# PCB.net
KiCad netlist of a schematic drawn in EAGLE
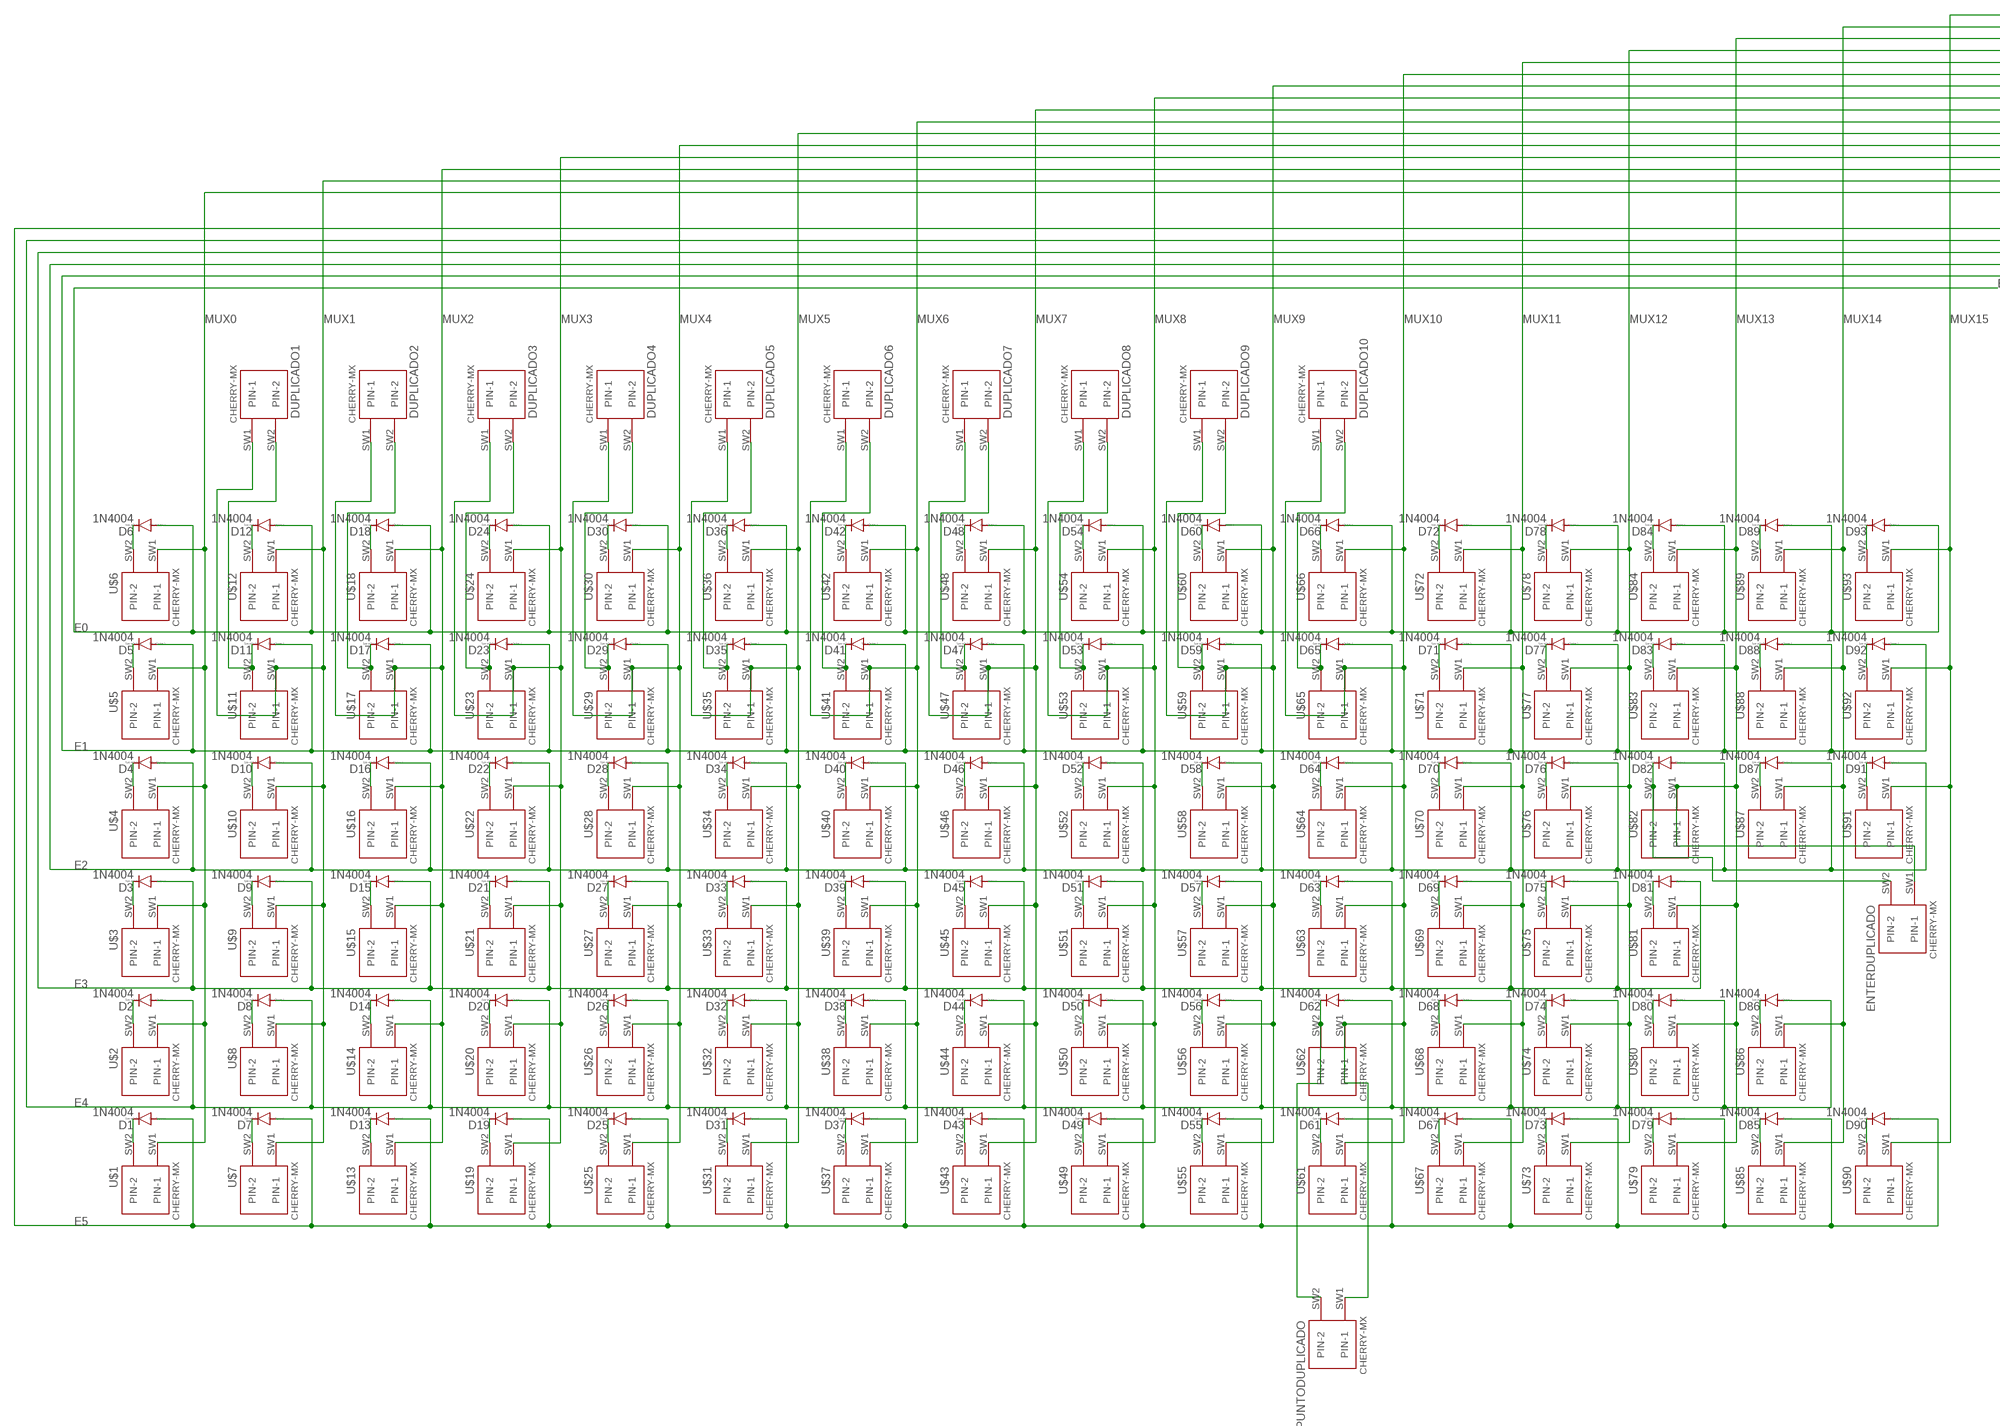
[diagram p0: schematic, sheet 1, part 1 of 2]
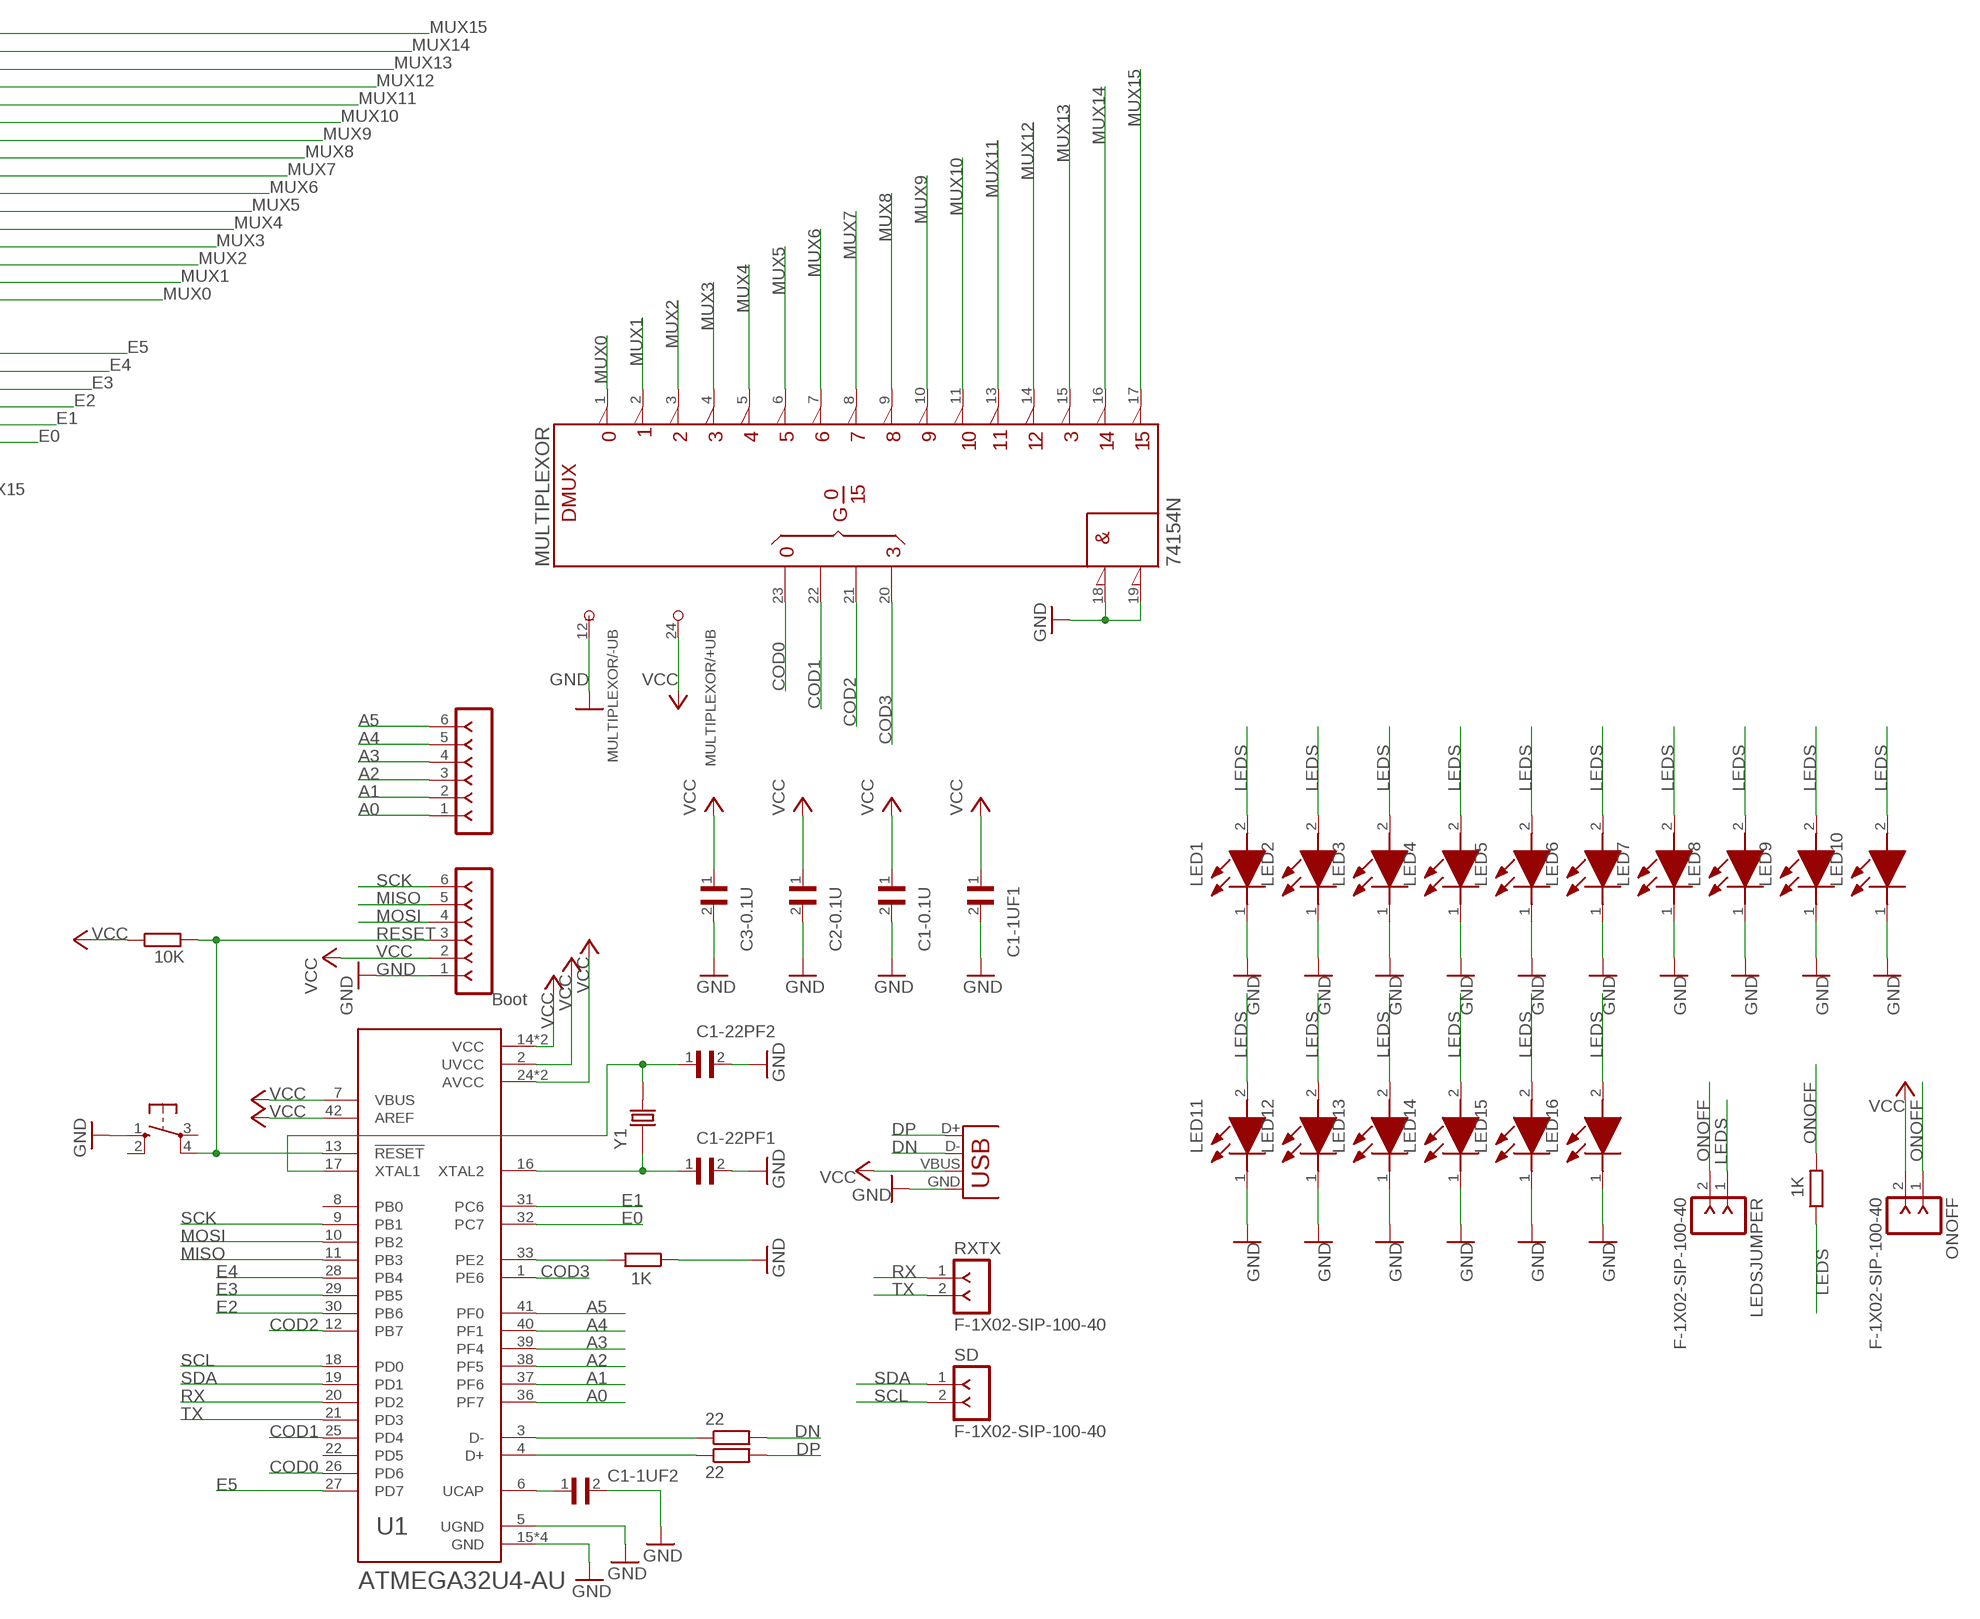
[diagram p1: schematic, sheet 1, part 2 of 2]

(export (version "E")
  (design (tool "Eeschema 10.0.6"))
  (components
    (comp (ref "ANALOG")
      (value "Boot")
      (footprint "eagle-import:SIP-100-06-32")
      (libsource (lib "eagle-import") (part "F-1X06-SIP-100-32"))
    )
    (comp (ref "BUTTON")
      (value "10-XX")
      (footprint "eagle-import:B3F-10XX")
      (fields (field (name "MPN") "B3F-1000"))
      (libsource (lib "eagle-import") (part "10-XX"))
    )
    (comp (ref "C1-0.1U")
      (value "RDE5C1H273J2M1H03A")
      (footprint "eagle-import:CAP_RDE5C1H273J2M1H03A")
      (fields (field (name "MF") "Murata Electronics"))
      (libsource (lib "eagle-import") (part "RDE5C1H273J2M1H03A"))
    )
    (comp (ref "C1-1UF1")
      (value "RDE5C1H273J2M1H03A")
      (footprint "eagle-import:CAP_RDE5C1H273J2M1H03A")
      (fields (field (name "MF") "Murata Electronics"))
      (libsource (lib "eagle-import") (part "RDE5C1H273J2M1H03A"))
    )
    (comp (ref "C1-1UF2")
      (value "RDE5C1H273J2M1H03A")
      (footprint "eagle-import:CAP_RDE5C1H273J2M1H03A")
      (fields (field (name "MF") "Murata Electronics"))
      (libsource (lib "eagle-import") (part "RDE5C1H273J2M1H03A"))
    )
    (comp (ref "C1-22PF1")
      (value "RDE5C1H273J2M1H03A")
      (footprint "eagle-import:CAP_RDE5C1H273J2M1H03A")
      (fields (field (name "MF") "Murata Electronics"))
      (libsource (lib "eagle-import") (part "RDE5C1H273J2M1H03A"))
    )
    (comp (ref "C1-22PF2")
      (value "RDE5C1H273J2M1H03A")
      (footprint "eagle-import:CAP_RDE5C1H273J2M1H03A")
      (fields (field (name "MF") "Murata Electronics"))
      (libsource (lib "eagle-import") (part "RDE5C1H273J2M1H03A"))
    )
    (comp (ref "C2-0.1U")
      (value "RDE5C1H273J2M1H03A")
      (footprint "eagle-import:CAP_RDE5C1H273J2M1H03A")
      (fields (field (name "MF") "Murata Electronics"))
      (libsource (lib "eagle-import") (part "RDE5C1H273J2M1H03A"))
    )
    (comp (ref "C3-0.1U")
      (value "RDE5C1H273J2M1H03A")
      (footprint "eagle-import:CAP_RDE5C1H273J2M1H03A")
      (fields (field (name "MF") "Murata Electronics"))
      (libsource (lib "eagle-import") (part "RDE5C1H273J2M1H03A"))
    )
    (comp (ref "D1")
      (value "1N4004")
      (footprint "eagle-import:DO41-10")
      (libsource (lib "eagle-import") (part "1N4004"))
    )
    (comp (ref "D2")
      (value "1N4004")
      (footprint "eagle-import:DO41-10")
      (libsource (lib "eagle-import") (part "1N4004"))
    )
    (comp (ref "D3")
      (value "1N4004")
      (footprint "eagle-import:DO41-10")
      (libsource (lib "eagle-import") (part "1N4004"))
    )
    (comp (ref "D4")
      (value "1N4004")
      (footprint "eagle-import:DO41-10")
      (libsource (lib "eagle-import") (part "1N4004"))
    )
    (comp (ref "D5")
      (value "1N4004")
      (footprint "eagle-import:DO41-10")
      (libsource (lib "eagle-import") (part "1N4004"))
    )
    (comp (ref "D6")
      (value "1N4004")
      (footprint "eagle-import:DO41-10")
      (libsource (lib "eagle-import") (part "1N4004"))
    )
    (comp (ref "D7")
      (value "1N4004")
      (footprint "eagle-import:DO41-10")
      (libsource (lib "eagle-import") (part "1N4004"))
    )
    (comp (ref "D8")
      (value "1N4004")
      (footprint "eagle-import:DO41-10")
      (libsource (lib "eagle-import") (part "1N4004"))
    )
    (comp (ref "D9")
      (value "1N4004")
      (footprint "eagle-import:DO41-10")
      (libsource (lib "eagle-import") (part "1N4004"))
    )
    (comp (ref "D10")
      (value "1N4004")
      (footprint "eagle-import:DO41-10")
      (libsource (lib "eagle-import") (part "1N4004"))
    )
    (comp (ref "D11")
      (value "1N4004")
      (footprint "eagle-import:DO41-10")
      (libsource (lib "eagle-import") (part "1N4004"))
    )
    (comp (ref "D12")
      (value "1N4004")
      (footprint "eagle-import:DO41-10")
      (libsource (lib "eagle-import") (part "1N4004"))
    )
    (comp (ref "D13")
      (value "1N4004")
      (footprint "eagle-import:DO41-10")
      (libsource (lib "eagle-import") (part "1N4004"))
    )
    (comp (ref "D14")
      (value "1N4004")
      (footprint "eagle-import:DO41-10")
      (libsource (lib "eagle-import") (part "1N4004"))
    )
    (comp (ref "D15")
      (value "1N4004")
      (footprint "eagle-import:DO41-10")
      (libsource (lib "eagle-import") (part "1N4004"))
    )
    (comp (ref "D16")
      (value "1N4004")
      (footprint "eagle-import:DO41-10")
      (libsource (lib "eagle-import") (part "1N4004"))
    )
    (comp (ref "D17")
      (value "1N4004")
      (footprint "eagle-import:DO41-10")
      (libsource (lib "eagle-import") (part "1N4004"))
    )
    (comp (ref "D18")
      (value "1N4004")
      (footprint "eagle-import:DO41-10")
      (libsource (lib "eagle-import") (part "1N4004"))
    )
    (comp (ref "D19")
      (value "1N4004")
      (footprint "eagle-import:DO41-10")
      (libsource (lib "eagle-import") (part "1N4004"))
    )
    (comp (ref "D20")
      (value "1N4004")
      (footprint "eagle-import:DO41-10")
      (libsource (lib "eagle-import") (part "1N4004"))
    )
    (comp (ref "D21")
      (value "1N4004")
      (footprint "eagle-import:DO41-10")
      (libsource (lib "eagle-import") (part "1N4004"))
    )
    (comp (ref "D22")
      (value "1N4004")
      (footprint "eagle-import:DO41-10")
      (libsource (lib "eagle-import") (part "1N4004"))
    )
    (comp (ref "D23")
      (value "1N4004")
      (footprint "eagle-import:DO41-10")
      (libsource (lib "eagle-import") (part "1N4004"))
    )
    (comp (ref "D24")
      (value "1N4004")
      (footprint "eagle-import:DO41-10")
      (libsource (lib "eagle-import") (part "1N4004"))
    )
    (comp (ref "D25")
      (value "1N4004")
      (footprint "eagle-import:DO41-10")
      (libsource (lib "eagle-import") (part "1N4004"))
    )
    (comp (ref "D26")
      (value "1N4004")
      (footprint "eagle-import:DO41-10")
      (libsource (lib "eagle-import") (part "1N4004"))
    )
    (comp (ref "D27")
      (value "1N4004")
      (footprint "eagle-import:DO41-10")
      (libsource (lib "eagle-import") (part "1N4004"))
    )
    (comp (ref "D28")
      (value "1N4004")
      (footprint "eagle-import:DO41-10")
      (libsource (lib "eagle-import") (part "1N4004"))
    )
    (comp (ref "D29")
      (value "1N4004")
      (footprint "eagle-import:DO41-10")
      (libsource (lib "eagle-import") (part "1N4004"))
    )
    (comp (ref "D30")
      (value "1N4004")
      (footprint "eagle-import:DO41-10")
      (libsource (lib "eagle-import") (part "1N4004"))
    )
    (comp (ref "D31")
      (value "1N4004")
      (footprint "eagle-import:DO41-10")
      (libsource (lib "eagle-import") (part "1N4004"))
    )
    (comp (ref "D32")
      (value "1N4004")
      (footprint "eagle-import:DO41-10")
      (libsource (lib "eagle-import") (part "1N4004"))
    )
    (comp (ref "D33")
      (value "1N4004")
      (footprint "eagle-import:DO41-10")
      (libsource (lib "eagle-import") (part "1N4004"))
    )
    (comp (ref "D34")
      (value "1N4004")
      (footprint "eagle-import:DO41-10")
      (libsource (lib "eagle-import") (part "1N4004"))
    )
    (comp (ref "D35")
      (value "1N4004")
      (footprint "eagle-import:DO41-10")
      (libsource (lib "eagle-import") (part "1N4004"))
    )
    (comp (ref "D36")
      (value "1N4004")
      (footprint "eagle-import:DO41-10")
      (libsource (lib "eagle-import") (part "1N4004"))
    )
    (comp (ref "D37")
      (value "1N4004")
      (footprint "eagle-import:DO41-10")
      (libsource (lib "eagle-import") (part "1N4004"))
    )
    (comp (ref "D38")
      (value "1N4004")
      (footprint "eagle-import:DO41-10")
      (libsource (lib "eagle-import") (part "1N4004"))
    )
    (comp (ref "D39")
      (value "1N4004")
      (footprint "eagle-import:DO41-10")
      (libsource (lib "eagle-import") (part "1N4004"))
    )
    (comp (ref "D40")
      (value "1N4004")
      (footprint "eagle-import:DO41-10")
      (libsource (lib "eagle-import") (part "1N4004"))
    )
    (comp (ref "D41")
      (value "1N4004")
      (footprint "eagle-import:DO41-10")
      (libsource (lib "eagle-import") (part "1N4004"))
    )
    (comp (ref "D42")
      (value "1N4004")
      (footprint "eagle-import:DO41-10")
      (libsource (lib "eagle-import") (part "1N4004"))
    )
    (comp (ref "D43")
      (value "1N4004")
      (footprint "eagle-import:DO41-10")
      (libsource (lib "eagle-import") (part "1N4004"))
    )
    (comp (ref "D44")
      (value "1N4004")
      (footprint "eagle-import:DO41-10")
      (libsource (lib "eagle-import") (part "1N4004"))
    )
    (comp (ref "D45")
      (value "1N4004")
      (footprint "eagle-import:DO41-10")
      (libsource (lib "eagle-import") (part "1N4004"))
    )
    (comp (ref "D46")
      (value "1N4004")
      (footprint "eagle-import:DO41-10")
      (libsource (lib "eagle-import") (part "1N4004"))
    )
    (comp (ref "D47")
      (value "1N4004")
      (footprint "eagle-import:DO41-10")
      (libsource (lib "eagle-import") (part "1N4004"))
    )
    (comp (ref "D48")
      (value "1N4004")
      (footprint "eagle-import:DO41-10")
      (libsource (lib "eagle-import") (part "1N4004"))
    )
    (comp (ref "D49")
      (value "1N4004")
      (footprint "eagle-import:DO41-10")
      (libsource (lib "eagle-import") (part "1N4004"))
    )
    (comp (ref "D50")
      (value "1N4004")
      (footprint "eagle-import:DO41-10")
      (libsource (lib "eagle-import") (part "1N4004"))
    )
    (comp (ref "D51")
      (value "1N4004")
      (footprint "eagle-import:DO41-10")
      (libsource (lib "eagle-import") (part "1N4004"))
    )
    (comp (ref "D52")
      (value "1N4004")
      (footprint "eagle-import:DO41-10")
      (libsource (lib "eagle-import") (part "1N4004"))
    )
    (comp (ref "D53")
      (value "1N4004")
      (footprint "eagle-import:DO41-10")
      (libsource (lib "eagle-import") (part "1N4004"))
    )
    (comp (ref "D54")
      (value "1N4004")
      (footprint "eagle-import:DO41-10")
      (libsource (lib "eagle-import") (part "1N4004"))
    )
    (comp (ref "D55")
      (value "1N4004")
      (footprint "eagle-import:DO41-10")
      (libsource (lib "eagle-import") (part "1N4004"))
    )
    (comp (ref "D56")
      (value "1N4004")
      (footprint "eagle-import:DO41-10")
      (libsource (lib "eagle-import") (part "1N4004"))
    )
    (comp (ref "D57")
      (value "1N4004")
      (footprint "eagle-import:DO41-10")
      (libsource (lib "eagle-import") (part "1N4004"))
    )
    (comp (ref "D58")
      (value "1N4004")
      (footprint "eagle-import:DO41-10")
      (libsource (lib "eagle-import") (part "1N4004"))
    )
    (comp (ref "D59")
      (value "1N4004")
      (footprint "eagle-import:DO41-10")
      (libsource (lib "eagle-import") (part "1N4004"))
    )
    (comp (ref "D60")
      (value "1N4004")
      (footprint "eagle-import:DO41-10")
      (libsource (lib "eagle-import") (part "1N4004"))
    )
    (comp (ref "D61")
      (value "1N4004")
      (footprint "eagle-import:DO41-10")
      (libsource (lib "eagle-import") (part "1N4004"))
    )
    (comp (ref "D62")
      (value "1N4004")
      (footprint "eagle-import:DO41-10")
      (libsource (lib "eagle-import") (part "1N4004"))
    )
    (comp (ref "D63")
      (value "1N4004")
      (footprint "eagle-import:DO41-10")
      (libsource (lib "eagle-import") (part "1N4004"))
    )
    (comp (ref "D64")
      (value "1N4004")
      (footprint "eagle-import:DO41-10")
      (libsource (lib "eagle-import") (part "1N4004"))
    )
    (comp (ref "D65")
      (value "1N4004")
      (footprint "eagle-import:DO41-10")
      (libsource (lib "eagle-import") (part "1N4004"))
    )
    (comp (ref "D66")
      (value "1N4004")
      (footprint "eagle-import:DO41-10")
      (libsource (lib "eagle-import") (part "1N4004"))
    )
    (comp (ref "D67")
      (value "1N4004")
      (footprint "eagle-import:DO41-10")
      (libsource (lib "eagle-import") (part "1N4004"))
    )
    (comp (ref "D68")
      (value "1N4004")
      (footprint "eagle-import:DO41-10")
      (libsource (lib "eagle-import") (part "1N4004"))
    )
    (comp (ref "D69")
      (value "1N4004")
      (footprint "eagle-import:DO41-10")
      (libsource (lib "eagle-import") (part "1N4004"))
    )
    (comp (ref "D70")
      (value "1N4004")
      (footprint "eagle-import:DO41-10")
      (libsource (lib "eagle-import") (part "1N4004"))
    )
    (comp (ref "D71")
      (value "1N4004")
      (footprint "eagle-import:DO41-10")
      (libsource (lib "eagle-import") (part "1N4004"))
    )
    (comp (ref "D72")
      (value "1N4004")
      (footprint "eagle-import:DO41-10")
      (libsource (lib "eagle-import") (part "1N4004"))
    )
    (comp (ref "D73")
      (value "1N4004")
      (footprint "eagle-import:DO41-10")
      (libsource (lib "eagle-import") (part "1N4004"))
    )
    (comp (ref "D74")
      (value "1N4004")
      (footprint "eagle-import:DO41-10")
      (libsource (lib "eagle-import") (part "1N4004"))
    )
    (comp (ref "D75")
      (value "1N4004")
      (footprint "eagle-import:DO41-10")
      (libsource (lib "eagle-import") (part "1N4004"))
    )
    (comp (ref "D76")
      (value "1N4004")
      (footprint "eagle-import:DO41-10")
      (libsource (lib "eagle-import") (part "1N4004"))
    )
    (comp (ref "D77")
      (value "1N4004")
      (footprint "eagle-import:DO41-10")
      (libsource (lib "eagle-import") (part "1N4004"))
    )
    (comp (ref "D78")
      (value "1N4004")
      (footprint "eagle-import:DO41-10")
      (libsource (lib "eagle-import") (part "1N4004"))
    )
    (comp (ref "D79")
      (value "1N4004")
      (footprint "eagle-import:DO41-10")
      (libsource (lib "eagle-import") (part "1N4004"))
    )
    (comp (ref "D80")
      (value "1N4004")
      (footprint "eagle-import:DO41-10")
      (libsource (lib "eagle-import") (part "1N4004"))
    )
    (comp (ref "D81")
      (value "1N4004")
      (footprint "eagle-import:DO41-10")
      (libsource (lib "eagle-import") (part "1N4004"))
    )
    (comp (ref "D82")
      (value "1N4004")
      (footprint "eagle-import:DO41-10")
      (libsource (lib "eagle-import") (part "1N4004"))
    )
    (comp (ref "D83")
      (value "1N4004")
      (footprint "eagle-import:DO41-10")
      (libsource (lib "eagle-import") (part "1N4004"))
    )
    (comp (ref "D84")
      (value "1N4004")
      (footprint "eagle-import:DO41-10")
      (libsource (lib "eagle-import") (part "1N4004"))
    )
    (comp (ref "D85")
      (value "1N4004")
      (footprint "eagle-import:DO41-10")
      (libsource (lib "eagle-import") (part "1N4004"))
    )
    (comp (ref "D86")
      (value "1N4004")
      (footprint "eagle-import:DO41-10")
      (libsource (lib "eagle-import") (part "1N4004"))
    )
    (comp (ref "D87")
      (value "1N4004")
      (footprint "eagle-import:DO41-10")
      (libsource (lib "eagle-import") (part "1N4004"))
    )
    (comp (ref "D88")
      (value "1N4004")
      (footprint "eagle-import:DO41-10")
      (libsource (lib "eagle-import") (part "1N4004"))
    )
    (comp (ref "D89")
      (value "1N4004")
      (footprint "eagle-import:DO41-10")
      (libsource (lib "eagle-import") (part "1N4004"))
    )
    (comp (ref "D90")
      (value "1N4004")
      (footprint "eagle-import:DO41-10")
      (libsource (lib "eagle-import") (part "1N4004"))
    )
    (comp (ref "D91")
      (value "1N4004")
      (footprint "eagle-import:DO41-10")
      (libsource (lib "eagle-import") (part "1N4004"))
    )
    (comp (ref "D92")
      (value "1N4004")
      (footprint "eagle-import:DO41-10")
      (libsource (lib "eagle-import") (part "1N4004"))
    )
    (comp (ref "D93")
      (value "1N4004")
      (footprint "eagle-import:DO41-10")
      (libsource (lib "eagle-import") (part "1N4004"))
    )
    (comp (ref "DUPLICADO1")
      (value "CHERRY-MX")
      (footprint "eagle-import:CHERRY-MX")
      (libsource (lib "eagle-import") (part "CHERRY-MX"))
    )
    (comp (ref "DUPLICADO2")
      (value "CHERRY-MX")
      (footprint "eagle-import:CHERRY-MX")
      (libsource (lib "eagle-import") (part "CHERRY-MX"))
    )
    (comp (ref "DUPLICADO3")
      (value "CHERRY-MX")
      (footprint "eagle-import:CHERRY-MX")
      (libsource (lib "eagle-import") (part "CHERRY-MX"))
    )
    (comp (ref "DUPLICADO4")
      (value "CHERRY-MX")
      (footprint "eagle-import:CHERRY-MX")
      (libsource (lib "eagle-import") (part "CHERRY-MX"))
    )
    (comp (ref "DUPLICADO5")
      (value "CHERRY-MX")
      (footprint "eagle-import:CHERRY-MX")
      (libsource (lib "eagle-import") (part "CHERRY-MX"))
    )
    (comp (ref "DUPLICADO6")
      (value "CHERRY-MX")
      (footprint "eagle-import:CHERRY-MX")
      (libsource (lib "eagle-import") (part "CHERRY-MX"))
    )
    (comp (ref "DUPLICADO7")
      (value "CHERRY-MX")
      (footprint "eagle-import:CHERRY-MX")
      (libsource (lib "eagle-import") (part "CHERRY-MX"))
    )
    (comp (ref "DUPLICADO8")
      (value "CHERRY-MX")
      (footprint "eagle-import:CHERRY-MX")
      (libsource (lib "eagle-import") (part "CHERRY-MX"))
    )
    (comp (ref "DUPLICADO9")
      (value "CHERRY-MX")
      (footprint "eagle-import:CHERRY-MX")
      (libsource (lib "eagle-import") (part "CHERRY-MX"))
    )
    (comp (ref "DUPLICADO10")
      (value "CHERRY-MX")
      (footprint "eagle-import:CHERRY-MX")
      (libsource (lib "eagle-import") (part "CHERRY-MX"))
    )
    (comp (ref "ENTERDUPLICADO")
      (value "CHERRY-MX")
      (footprint "eagle-import:CHERRY-MX")
      (libsource (lib "eagle-import") (part "CHERRY-MX"))
    )
    (comp (ref "J3")
      (value "Boot")
      (footprint "eagle-import:SIP-100-06-32")
      (libsource (lib "eagle-import") (part "F-1X06-SIP-100-32"))
    )
    (comp (ref "LED1")
      (value "ASMM-CA03-AS402")
      (footprint "eagle-import:LEDM3528X200N")
      (libsource (lib "eagle-import") (part "ASMM-CA03-AS402"))
    )
    (comp (ref "LED2")
      (value "ASMM-CA03-AS402")
      (footprint "eagle-import:LEDM3528X200N")
      (libsource (lib "eagle-import") (part "ASMM-CA03-AS402"))
    )
    (comp (ref "LED3")
      (value "ASMM-CA03-AS402")
      (footprint "eagle-import:LEDM3528X200N")
      (libsource (lib "eagle-import") (part "ASMM-CA03-AS402"))
    )
    (comp (ref "LED4")
      (value "ASMM-CA03-AS402")
      (footprint "eagle-import:LEDM3528X200N")
      (libsource (lib "eagle-import") (part "ASMM-CA03-AS402"))
    )
    (comp (ref "LED5")
      (value "ASMM-CA03-AS402")
      (footprint "eagle-import:LEDM3528X200N")
      (libsource (lib "eagle-import") (part "ASMM-CA03-AS402"))
    )
    (comp (ref "LED6")
      (value "ASMM-CA03-AS402")
      (footprint "eagle-import:LEDM3528X200N")
      (libsource (lib "eagle-import") (part "ASMM-CA03-AS402"))
    )
    (comp (ref "LED7")
      (value "ASMM-CA03-AS402")
      (footprint "eagle-import:LEDM3528X200N")
      (libsource (lib "eagle-import") (part "ASMM-CA03-AS402"))
    )
    (comp (ref "LED8")
      (value "ASMM-CA03-AS402")
      (footprint "eagle-import:LEDM3528X200N")
      (libsource (lib "eagle-import") (part "ASMM-CA03-AS402"))
    )
    (comp (ref "LED9")
      (value "ASMM-CA03-AS402")
      (footprint "eagle-import:LEDM3528X200N")
      (libsource (lib "eagle-import") (part "ASMM-CA03-AS402"))
    )
    (comp (ref "LED10")
      (value "ASMM-CA03-AS402")
      (footprint "eagle-import:LEDM3528X200N")
      (libsource (lib "eagle-import") (part "ASMM-CA03-AS402"))
    )
    (comp (ref "LED11")
      (value "ASMM-CA03-AS402")
      (footprint "eagle-import:LEDM3528X200N")
      (libsource (lib "eagle-import") (part "ASMM-CA03-AS402"))
    )
    (comp (ref "LED12")
      (value "ASMM-CA03-AS402")
      (footprint "eagle-import:LEDM3528X200N")
      (libsource (lib "eagle-import") (part "ASMM-CA03-AS402"))
    )
    (comp (ref "LED13")
      (value "ASMM-CA03-AS402")
      (footprint "eagle-import:LEDM3528X200N")
      (libsource (lib "eagle-import") (part "ASMM-CA03-AS402"))
    )
    (comp (ref "LED14")
      (value "ASMM-CA03-AS402")
      (footprint "eagle-import:LEDM3528X200N")
      (libsource (lib "eagle-import") (part "ASMM-CA03-AS402"))
    )
    (comp (ref "LED15")
      (value "ASMM-CA03-AS402")
      (footprint "eagle-import:LEDM3528X200N")
      (libsource (lib "eagle-import") (part "ASMM-CA03-AS402"))
    )
    (comp (ref "LED16")
      (value "ASMM-CA03-AS402")
      (footprint "eagle-import:LEDM3528X200N")
      (libsource (lib "eagle-import") (part "ASMM-CA03-AS402"))
    )
    (comp (ref "LEDSJUMPER")
      (value "F-1X02-SIP-100-40")
      (footprint "eagle-import:SIP-100-02-40")
      (libsource (lib "eagle-import") (part "F-1X02-SIP-100-40"))
    )
    (comp (ref "MULTIPLEXOR")
      (value "74154N")
      (footprint "eagle-import:DIL24-3")
      (fields (field (name "SPICEPREFIX") "X"))
      (libsource (lib "eagle-import") (part "74154N"))
    )
    (comp (ref "ONOFF")
      (value "F-1X02-SIP-100-40")
      (footprint "eagle-import:SIP-100-02-40")
      (libsource (lib "eagle-import") (part "F-1X02-SIP-100-40"))
    )
    (comp (ref "PUNTODUPLICADO")
      (value "CHERRY-MX")
      (footprint "eagle-import:CHERRY-MX")
      (libsource (lib "eagle-import") (part "CHERRY-MX"))
    )
    (comp (ref "R1")
      (value "22")
      (footprint "eagle-import:0204_7")
      (libsource (lib "eagle-import") (part "R-EU_0204/7"))
    )
    (comp (ref "R2")
      (value "22")
      (footprint "eagle-import:0204_7")
      (libsource (lib "eagle-import") (part "R-EU_0204/7"))
    )
    (comp (ref "R3")
      (value "1K")
      (footprint "eagle-import:0204_7")
      (libsource (lib "eagle-import") (part "R-EU_0204/7"))
    )
    (comp (ref "R4")
      (value "1K")
      (footprint "eagle-import:0204_7")
      (libsource (lib "eagle-import") (part "R-EU_0204/7"))
    )
    (comp (ref "R5")
      (value "10K")
      (footprint "eagle-import:0204_7")
      (libsource (lib "eagle-import") (part "R-EU_0204/7"))
    )
    (comp (ref "RXTX")
      (value "F-1X02-SIP-100-40")
      (footprint "eagle-import:SIP-100-02-40")
      (libsource (lib "eagle-import") (part "F-1X02-SIP-100-40"))
    )
    (comp (ref "SD")
      (value "F-1X02-SIP-100-40")
      (footprint "eagle-import:SIP-100-02-40")
      (libsource (lib "eagle-import") (part "F-1X02-SIP-100-40"))
    )
    (comp (ref "U$1")
      (value "CHERRY-MX")
      (footprint "eagle-import:CHERRY-MX")
      (libsource (lib "eagle-import") (part "CHERRY-MX"))
    )
    (comp (ref "U$2")
      (value "CHERRY-MX")
      (footprint "eagle-import:CHERRY-MX")
      (libsource (lib "eagle-import") (part "CHERRY-MX"))
    )
    (comp (ref "U$3")
      (value "CHERRY-MX")
      (footprint "eagle-import:CHERRY-MX")
      (libsource (lib "eagle-import") (part "CHERRY-MX"))
    )
    (comp (ref "U$4")
      (value "CHERRY-MX")
      (footprint "eagle-import:CHERRY-MX")
      (libsource (lib "eagle-import") (part "CHERRY-MX"))
    )
    (comp (ref "U$5")
      (value "CHERRY-MX")
      (footprint "eagle-import:CHERRY-MX")
      (libsource (lib "eagle-import") (part "CHERRY-MX"))
    )
    (comp (ref "U$6")
      (value "CHERRY-MX")
      (footprint "eagle-import:CHERRY-MX")
      (libsource (lib "eagle-import") (part "CHERRY-MX"))
    )
    (comp (ref "U$7")
      (value "CHERRY-MX")
      (footprint "eagle-import:CHERRY-MX")
      (libsource (lib "eagle-import") (part "CHERRY-MX"))
    )
    (comp (ref "U$8")
      (value "CHERRY-MX")
      (footprint "eagle-import:CHERRY-MX")
      (libsource (lib "eagle-import") (part "CHERRY-MX"))
    )
    (comp (ref "U$9")
      (value "CHERRY-MX")
      (footprint "eagle-import:CHERRY-MX")
      (libsource (lib "eagle-import") (part "CHERRY-MX"))
    )
    (comp (ref "U$10")
      (value "CHERRY-MX")
      (footprint "eagle-import:CHERRY-MX")
      (libsource (lib "eagle-import") (part "CHERRY-MX"))
    )
    (comp (ref "U$11")
      (value "CHERRY-MX")
      (footprint "eagle-import:CHERRY-MX")
      (libsource (lib "eagle-import") (part "CHERRY-MX"))
    )
    (comp (ref "U$12")
      (value "CHERRY-MX")
      (footprint "eagle-import:CHERRY-MX")
      (libsource (lib "eagle-import") (part "CHERRY-MX"))
    )
    (comp (ref "U$13")
      (value "CHERRY-MX")
      (footprint "eagle-import:CHERRY-MX")
      (libsource (lib "eagle-import") (part "CHERRY-MX"))
    )
    (comp (ref "U$14")
      (value "CHERRY-MX")
      (footprint "eagle-import:CHERRY-MX")
      (libsource (lib "eagle-import") (part "CHERRY-MX"))
    )
    (comp (ref "U$15")
      (value "CHERRY-MX")
      (footprint "eagle-import:CHERRY-MX")
      (libsource (lib "eagle-import") (part "CHERRY-MX"))
    )
    (comp (ref "U$16")
      (value "CHERRY-MX")
      (footprint "eagle-import:CHERRY-MX")
      (libsource (lib "eagle-import") (part "CHERRY-MX"))
    )
    (comp (ref "U$17")
      (value "CHERRY-MX")
      (footprint "eagle-import:CHERRY-MX")
      (libsource (lib "eagle-import") (part "CHERRY-MX"))
    )
    (comp (ref "U$18")
      (value "CHERRY-MX")
      (footprint "eagle-import:CHERRY-MX")
      (libsource (lib "eagle-import") (part "CHERRY-MX"))
    )
    (comp (ref "U$19")
      (value "CHERRY-MX")
      (footprint "eagle-import:CHERRY-MX")
      (libsource (lib "eagle-import") (part "CHERRY-MX"))
    )
    (comp (ref "U$20")
      (value "CHERRY-MX")
      (footprint "eagle-import:CHERRY-MX")
      (libsource (lib "eagle-import") (part "CHERRY-MX"))
    )
    (comp (ref "U$21")
      (value "CHERRY-MX")
      (footprint "eagle-import:CHERRY-MX")
      (libsource (lib "eagle-import") (part "CHERRY-MX"))
    )
    (comp (ref "U$22")
      (value "CHERRY-MX")
      (footprint "eagle-import:CHERRY-MX")
      (libsource (lib "eagle-import") (part "CHERRY-MX"))
    )
    (comp (ref "U$23")
      (value "CHERRY-MX")
      (footprint "eagle-import:CHERRY-MX")
      (libsource (lib "eagle-import") (part "CHERRY-MX"))
    )
    (comp (ref "U$24")
      (value "CHERRY-MX")
      (footprint "eagle-import:CHERRY-MX")
      (libsource (lib "eagle-import") (part "CHERRY-MX"))
    )
    (comp (ref "U$25")
      (value "CHERRY-MX")
      (footprint "eagle-import:CHERRY-MX")
      (libsource (lib "eagle-import") (part "CHERRY-MX"))
    )
    (comp (ref "U$26")
      (value "CHERRY-MX")
      (footprint "eagle-import:CHERRY-MX")
      (libsource (lib "eagle-import") (part "CHERRY-MX"))
    )
    (comp (ref "U$27")
      (value "CHERRY-MX")
      (footprint "eagle-import:CHERRY-MX")
      (libsource (lib "eagle-import") (part "CHERRY-MX"))
    )
    (comp (ref "U$28")
      (value "CHERRY-MX")
      (footprint "eagle-import:CHERRY-MX")
      (libsource (lib "eagle-import") (part "CHERRY-MX"))
    )
    (comp (ref "U$29")
      (value "CHERRY-MX")
      (footprint "eagle-import:CHERRY-MX")
      (libsource (lib "eagle-import") (part "CHERRY-MX"))
    )
    (comp (ref "U$30")
      (value "CHERRY-MX")
      (footprint "eagle-import:CHERRY-MX")
      (libsource (lib "eagle-import") (part "CHERRY-MX"))
    )
    (comp (ref "U$31")
      (value "CHERRY-MX")
      (footprint "eagle-import:CHERRY-MX")
      (libsource (lib "eagle-import") (part "CHERRY-MX"))
    )
    (comp (ref "U$32")
      (value "CHERRY-MX")
      (footprint "eagle-import:CHERRY-MX")
      (libsource (lib "eagle-import") (part "CHERRY-MX"))
    )
    (comp (ref "U$33")
      (value "CHERRY-MX")
      (footprint "eagle-import:CHERRY-MX")
      (libsource (lib "eagle-import") (part "CHERRY-MX"))
    )
    (comp (ref "U$34")
      (value "CHERRY-MX")
      (footprint "eagle-import:CHERRY-MX")
      (libsource (lib "eagle-import") (part "CHERRY-MX"))
    )
    (comp (ref "U$35")
      (value "CHERRY-MX")
      (footprint "eagle-import:CHERRY-MX")
      (libsource (lib "eagle-import") (part "CHERRY-MX"))
    )
    (comp (ref "U$36")
      (value "CHERRY-MX")
      (footprint "eagle-import:CHERRY-MX")
      (libsource (lib "eagle-import") (part "CHERRY-MX"))
    )
    (comp (ref "U$37")
      (value "CHERRY-MX")
      (footprint "eagle-import:CHERRY-MX")
      (libsource (lib "eagle-import") (part "CHERRY-MX"))
    )
    (comp (ref "U$38")
      (value "CHERRY-MX")
      (footprint "eagle-import:CHERRY-MX")
      (libsource (lib "eagle-import") (part "CHERRY-MX"))
    )
    (comp (ref "U$39")
      (value "CHERRY-MX")
      (footprint "eagle-import:CHERRY-MX")
      (libsource (lib "eagle-import") (part "CHERRY-MX"))
    )
    (comp (ref "U$40")
      (value "CHERRY-MX")
      (footprint "eagle-import:CHERRY-MX")
      (libsource (lib "eagle-import") (part "CHERRY-MX"))
    )
    (comp (ref "U$41")
      (value "CHERRY-MX")
      (footprint "eagle-import:CHERRY-MX")
      (libsource (lib "eagle-import") (part "CHERRY-MX"))
    )
    (comp (ref "U$42")
      (value "CHERRY-MX")
      (footprint "eagle-import:CHERRY-MX")
      (libsource (lib "eagle-import") (part "CHERRY-MX"))
    )
    (comp (ref "U$43")
      (value "CHERRY-MX")
      (footprint "eagle-import:CHERRY-MX")
      (libsource (lib "eagle-import") (part "CHERRY-MX"))
    )
    (comp (ref "U$44")
      (value "CHERRY-MX")
      (footprint "eagle-import:CHERRY-MX")
      (libsource (lib "eagle-import") (part "CHERRY-MX"))
    )
    (comp (ref "U$45")
      (value "CHERRY-MX")
      (footprint "eagle-import:CHERRY-MX")
      (libsource (lib "eagle-import") (part "CHERRY-MX"))
    )
    (comp (ref "U$46")
      (value "CHERRY-MX")
      (footprint "eagle-import:CHERRY-MX")
      (libsource (lib "eagle-import") (part "CHERRY-MX"))
    )
    (comp (ref "U$47")
      (value "CHERRY-MX")
      (footprint "eagle-import:CHERRY-MX")
      (libsource (lib "eagle-import") (part "CHERRY-MX"))
    )
    (comp (ref "U$48")
      (value "CHERRY-MX")
      (footprint "eagle-import:CHERRY-MX")
      (libsource (lib "eagle-import") (part "CHERRY-MX"))
    )
    (comp (ref "U$49")
      (value "CHERRY-MX")
      (footprint "eagle-import:CHERRY-MX")
      (libsource (lib "eagle-import") (part "CHERRY-MX"))
    )
    (comp (ref "U$50")
      (value "CHERRY-MX")
      (footprint "eagle-import:CHERRY-MX")
      (libsource (lib "eagle-import") (part "CHERRY-MX"))
    )
    (comp (ref "U$51")
      (value "CHERRY-MX")
      (footprint "eagle-import:CHERRY-MX")
      (libsource (lib "eagle-import") (part "CHERRY-MX"))
    )
    (comp (ref "U$52")
      (value "CHERRY-MX")
      (footprint "eagle-import:CHERRY-MX")
      (libsource (lib "eagle-import") (part "CHERRY-MX"))
    )
    (comp (ref "U$53")
      (value "CHERRY-MX")
      (footprint "eagle-import:CHERRY-MX")
      (libsource (lib "eagle-import") (part "CHERRY-MX"))
    )
    (comp (ref "U$54")
      (value "CHERRY-MX")
      (footprint "eagle-import:CHERRY-MX")
      (libsource (lib "eagle-import") (part "CHERRY-MX"))
    )
    (comp (ref "U$55")
      (value "CHERRY-MX")
      (footprint "eagle-import:CHERRY-MX")
      (libsource (lib "eagle-import") (part "CHERRY-MX"))
    )
    (comp (ref "U$56")
      (value "CHERRY-MX")
      (footprint "eagle-import:CHERRY-MX")
      (libsource (lib "eagle-import") (part "CHERRY-MX"))
    )
    (comp (ref "U$57")
      (value "CHERRY-MX")
      (footprint "eagle-import:CHERRY-MX")
      (libsource (lib "eagle-import") (part "CHERRY-MX"))
    )
    (comp (ref "U$58")
      (value "CHERRY-MX")
      (footprint "eagle-import:CHERRY-MX")
      (libsource (lib "eagle-import") (part "CHERRY-MX"))
    )
    (comp (ref "U$59")
      (value "CHERRY-MX")
      (footprint "eagle-import:CHERRY-MX")
      (libsource (lib "eagle-import") (part "CHERRY-MX"))
    )
    (comp (ref "U$60")
      (value "CHERRY-MX")
      (footprint "eagle-import:CHERRY-MX")
      (libsource (lib "eagle-import") (part "CHERRY-MX"))
    )
    (comp (ref "U$61")
      (value "CHERRY-MX")
      (footprint "eagle-import:CHERRY-MX")
      (libsource (lib "eagle-import") (part "CHERRY-MX"))
    )
    (comp (ref "U$62")
      (value "CHERRY-MX")
      (footprint "eagle-import:CHERRY-MX")
      (libsource (lib "eagle-import") (part "CHERRY-MX"))
    )
    (comp (ref "U$63")
      (value "CHERRY-MX")
      (footprint "eagle-import:CHERRY-MX")
      (libsource (lib "eagle-import") (part "CHERRY-MX"))
    )
    (comp (ref "U$64")
      (value "CHERRY-MX")
      (footprint "eagle-import:CHERRY-MX")
      (libsource (lib "eagle-import") (part "CHERRY-MX"))
    )
    (comp (ref "U$65")
      (value "CHERRY-MX")
      (footprint "eagle-import:CHERRY-MX")
      (libsource (lib "eagle-import") (part "CHERRY-MX"))
    )
    (comp (ref "U$66")
      (value "CHERRY-MX")
      (footprint "eagle-import:CHERRY-MX")
      (libsource (lib "eagle-import") (part "CHERRY-MX"))
    )
    (comp (ref "U$67")
      (value "CHERRY-MX")
      (footprint "eagle-import:CHERRY-MX")
      (libsource (lib "eagle-import") (part "CHERRY-MX"))
    )
    (comp (ref "U$68")
      (value "CHERRY-MX")
      (footprint "eagle-import:CHERRY-MX")
      (libsource (lib "eagle-import") (part "CHERRY-MX"))
    )
    (comp (ref "U$69")
      (value "CHERRY-MX")
      (footprint "eagle-import:CHERRY-MX")
      (libsource (lib "eagle-import") (part "CHERRY-MX"))
    )
    (comp (ref "U$70")
      (value "CHERRY-MX")
      (footprint "eagle-import:CHERRY-MX")
      (libsource (lib "eagle-import") (part "CHERRY-MX"))
    )
    (comp (ref "U$71")
      (value "CHERRY-MX")
      (footprint "eagle-import:CHERRY-MX")
      (libsource (lib "eagle-import") (part "CHERRY-MX"))
    )
    (comp (ref "U$72")
      (value "CHERRY-MX")
      (footprint "eagle-import:CHERRY-MX")
      (libsource (lib "eagle-import") (part "CHERRY-MX"))
    )
    (comp (ref "U$73")
      (value "CHERRY-MX")
      (footprint "eagle-import:CHERRY-MX")
      (libsource (lib "eagle-import") (part "CHERRY-MX"))
    )
    (comp (ref "U$74")
      (value "CHERRY-MX")
      (footprint "eagle-import:CHERRY-MX")
      (libsource (lib "eagle-import") (part "CHERRY-MX"))
    )
    (comp (ref "U$75")
      (value "CHERRY-MX")
      (footprint "eagle-import:CHERRY-MX")
      (libsource (lib "eagle-import") (part "CHERRY-MX"))
    )
    (comp (ref "U$76")
      (value "CHERRY-MX")
      (footprint "eagle-import:CHERRY-MX")
      (libsource (lib "eagle-import") (part "CHERRY-MX"))
    )
    (comp (ref "U$77")
      (value "CHERRY-MX")
      (footprint "eagle-import:CHERRY-MX")
      (libsource (lib "eagle-import") (part "CHERRY-MX"))
    )
    (comp (ref "U$78")
      (value "CHERRY-MX")
      (footprint "eagle-import:CHERRY-MX")
      (libsource (lib "eagle-import") (part "CHERRY-MX"))
    )
    (comp (ref "U$79")
      (value "CHERRY-MX")
      (footprint "eagle-import:CHERRY-MX")
      (libsource (lib "eagle-import") (part "CHERRY-MX"))
    )
    (comp (ref "U$80")
      (value "CHERRY-MX")
      (footprint "eagle-import:CHERRY-MX")
      (libsource (lib "eagle-import") (part "CHERRY-MX"))
    )
    (comp (ref "U$81")
      (value "CHERRY-MX")
      (footprint "eagle-import:CHERRY-MX")
      (libsource (lib "eagle-import") (part "CHERRY-MX"))
    )
    (comp (ref "U$82")
      (value "CHERRY-MX")
      (footprint "eagle-import:CHERRY-MX")
      (libsource (lib "eagle-import") (part "CHERRY-MX"))
    )
    (comp (ref "U$83")
      (value "CHERRY-MX")
      (footprint "eagle-import:CHERRY-MX")
      (libsource (lib "eagle-import") (part "CHERRY-MX"))
    )
    (comp (ref "U$84")
      (value "CHERRY-MX")
      (footprint "eagle-import:CHERRY-MX")
      (libsource (lib "eagle-import") (part "CHERRY-MX"))
    )
    (comp (ref "U$85")
      (value "CHERRY-MX")
      (footprint "eagle-import:CHERRY-MX")
      (libsource (lib "eagle-import") (part "CHERRY-MX"))
    )
    (comp (ref "U$86")
      (value "CHERRY-MX")
      (footprint "eagle-import:CHERRY-MX")
      (libsource (lib "eagle-import") (part "CHERRY-MX"))
    )
    (comp (ref "U$87")
      (value "CHERRY-MX")
      (footprint "eagle-import:CHERRY-MX")
      (libsource (lib "eagle-import") (part "CHERRY-MX"))
    )
    (comp (ref "U$88")
      (value "CHERRY-MX")
      (footprint "eagle-import:CHERRY-MX")
      (libsource (lib "eagle-import") (part "CHERRY-MX"))
    )
    (comp (ref "U$89")
      (value "CHERRY-MX")
      (footprint "eagle-import:CHERRY-MX")
      (libsource (lib "eagle-import") (part "CHERRY-MX"))
    )
    (comp (ref "U$90")
      (value "CHERRY-MX")
      (footprint "eagle-import:CHERRY-MX")
      (libsource (lib "eagle-import") (part "CHERRY-MX"))
    )
    (comp (ref "U$91")
      (value "CHERRY-MX")
      (footprint "eagle-import:CHERRY-MX")
      (libsource (lib "eagle-import") (part "CHERRY-MX"))
    )
    (comp (ref "U$92")
      (value "CHERRY-MX")
      (footprint "eagle-import:CHERRY-MX")
      (libsource (lib "eagle-import") (part "CHERRY-MX"))
    )
    (comp (ref "U$93")
      (value "CHERRY-MX")
      (footprint "eagle-import:CHERRY-MX")
      (libsource (lib "eagle-import") (part "CHERRY-MX"))
    )
    (comp (ref "U1")
      (value "ATMEGA32U4-AU")
      (footprint "eagle-import:QFP80P1200X1200X120-44N")
      (fields (field (name "MF") "Microchip"))
      (libsource (lib "eagle-import") (part "ATMEGA32U4-AU"))
    )
    (comp (ref "X2")
      (value "USB-A-H")
      (footprint "eagle-import:USB-A-H")
      (libsource (lib "eagle-import") (part "USB-A-H"))
    )
    (comp (ref "Y1")
      (value "ECS-160-20-4X")
      (footprint "eagle-import:XTAL_ECS-160-20-4X")
      (fields (field (name "MF") "ECS Inc."))
      (libsource (lib "eagle-import") (part "ECS-160-20-4X"))
    )
  )
  (nets
    (net (code "1") (name "/A0") (class "Default")
      (node (ref "ANALOG") (pin "1") (pinfunction "1_1") (pintype "passive"))
      (node (ref "U1") (pin "36") (pinfunction "PF7_36") (pintype "bidirectional"))
    )
    (net (code "2") (name "/A1") (class "Default")
      (node (ref "ANALOG") (pin "2") (pinfunction "2_2") (pintype "passive"))
      (node (ref "U1") (pin "37") (pinfunction "PF6_37") (pintype "bidirectional"))
    )
    (net (code "3") (name "/A2") (class "Default")
      (node (ref "ANALOG") (pin "3") (pinfunction "3_3") (pintype "passive"))
      (node (ref "U1") (pin "38") (pinfunction "PF5_38") (pintype "bidirectional"))
    )
    (net (code "4") (name "/A3") (class "Default")
      (node (ref "ANALOG") (pin "4") (pinfunction "4_4") (pintype "passive"))
      (node (ref "U1") (pin "39") (pinfunction "PF4_39") (pintype "bidirectional"))
    )
    (net (code "5") (name "/A4") (class "Default")
      (node (ref "ANALOG") (pin "5") (pinfunction "5_5") (pintype "passive"))
      (node (ref "U1") (pin "40") (pinfunction "PF1_40") (pintype "bidirectional"))
    )
    (net (code "6") (name "/A5") (class "Default")
      (node (ref "ANALOG") (pin "6") (pinfunction "6_6") (pintype "passive"))
      (node (ref "U1") (pin "41") (pinfunction "PF0_41") (pintype "bidirectional"))
    )
    (net (code "7") (name "/COD0") (class "Default")
      (node (ref "MULTIPLEXOR") (pin "23") (pinfunction "A_23") (pintype "input"))
      (node (ref "U1") (pin "26") (pinfunction "PD6_26") (pintype "bidirectional"))
    )
    (net (code "8") (name "/COD1") (class "Default")
      (node (ref "MULTIPLEXOR") (pin "22") (pinfunction "B_22") (pintype "input"))
      (node (ref "U1") (pin "25") (pinfunction "PD4_25") (pintype "bidirectional"))
    )
    (net (code "9") (name "/COD2") (class "Default")
      (node (ref "MULTIPLEXOR") (pin "21") (pinfunction "C_21") (pintype "input"))
      (node (ref "U1") (pin "12") (pinfunction "PB7_12") (pintype "bidirectional"))
    )
    (net (code "10") (name "/COD3") (class "Default")
      (node (ref "MULTIPLEXOR") (pin "20") (pinfunction "D_20") (pintype "input"))
      (node (ref "U1") (pin "1") (pinfunction "PE6_1") (pintype "bidirectional"))
    )
    (net (code "11") (name "/DN") (class "Default")
      (node (ref "R2") (pin "2") (pinfunction "2_2") (pintype "passive"))
      (node (ref "X2") (pin "D-") (pinfunction "D-_D-") (pintype "bidirectional"))
    )
    (net (code "12") (name "/DP") (class "Default")
      (node (ref "R1") (pin "2") (pinfunction "2_2") (pintype "passive"))
      (node (ref "X2") (pin "D+") (pinfunction "D+_D+") (pintype "bidirectional"))
    )
    (net (code "13") (name "/E0") (class "Default")
      (node (ref "D12") (pin "A") (pinfunction "A_A") (pintype "passive"))
      (node (ref "D18") (pin "A") (pinfunction "A_A") (pintype "passive"))
      (node (ref "D24") (pin "A") (pinfunction "A_A") (pintype "passive"))
      (node (ref "D30") (pin "A") (pinfunction "A_A") (pintype "passive"))
      (node (ref "D36") (pin "A") (pinfunction "A_A") (pintype "passive"))
      (node (ref "D42") (pin "A") (pinfunction "A_A") (pintype "passive"))
      (node (ref "D48") (pin "A") (pinfunction "A_A") (pintype "passive"))
      (node (ref "D54") (pin "A") (pinfunction "A_A") (pintype "passive"))
      (node (ref "D6") (pin "A") (pinfunction "A_A") (pintype "passive"))
      (node (ref "D60") (pin "A") (pinfunction "A_A") (pintype "passive"))
      (node (ref "D66") (pin "A") (pinfunction "A_A") (pintype "passive"))
      (node (ref "D72") (pin "A") (pinfunction "A_A") (pintype "passive"))
      (node (ref "D78") (pin "A") (pinfunction "A_A") (pintype "passive"))
      (node (ref "D84") (pin "A") (pinfunction "A_A") (pintype "passive"))
      (node (ref "D89") (pin "A") (pinfunction "A_A") (pintype "passive"))
      (node (ref "D93") (pin "A") (pinfunction "A_A") (pintype "passive"))
      (node (ref "U1") (pin "32") (pinfunction "PC7_32") (pintype "bidirectional"))
    )
    (net (code "14") (name "/E1") (class "Default")
      (node (ref "D11") (pin "A") (pinfunction "A_A") (pintype "passive"))
      (node (ref "D17") (pin "A") (pinfunction "A_A") (pintype "passive"))
      (node (ref "D23") (pin "A") (pinfunction "A_A") (pintype "passive"))
      (node (ref "D29") (pin "A") (pinfunction "A_A") (pintype "passive"))
      (node (ref "D35") (pin "A") (pinfunction "A_A") (pintype "passive"))
      (node (ref "D41") (pin "A") (pinfunction "A_A") (pintype "passive"))
      (node (ref "D47") (pin "A") (pinfunction "A_A") (pintype "passive"))
      (node (ref "D5") (pin "A") (pinfunction "A_A") (pintype "passive"))
      (node (ref "D53") (pin "A") (pinfunction "A_A") (pintype "passive"))
      (node (ref "D59") (pin "A") (pinfunction "A_A") (pintype "passive"))
      (node (ref "D65") (pin "A") (pinfunction "A_A") (pintype "passive"))
      (node (ref "D71") (pin "A") (pinfunction "A_A") (pintype "passive"))
      (node (ref "D77") (pin "A") (pinfunction "A_A") (pintype "passive"))
      (node (ref "D83") (pin "A") (pinfunction "A_A") (pintype "passive"))
      (node (ref "D88") (pin "A") (pinfunction "A_A") (pintype "passive"))
      (node (ref "D92") (pin "A") (pinfunction "A_A") (pintype "passive"))
      (node (ref "U1") (pin "31") (pinfunction "PC6_31") (pintype "bidirectional"))
    )
    (net (code "15") (name "/E2") (class "Default")
      (node (ref "D10") (pin "A") (pinfunction "A_A") (pintype "passive"))
      (node (ref "D16") (pin "A") (pinfunction "A_A") (pintype "passive"))
      (node (ref "D22") (pin "A") (pinfunction "A_A") (pintype "passive"))
      (node (ref "D28") (pin "A") (pinfunction "A_A") (pintype "passive"))
      (node (ref "D34") (pin "A") (pinfunction "A_A") (pintype "passive"))
      (node (ref "D4") (pin "A") (pinfunction "A_A") (pintype "passive"))
      (node (ref "D40") (pin "A") (pinfunction "A_A") (pintype "passive"))
      (node (ref "D46") (pin "A") (pinfunction "A_A") (pintype "passive"))
      (node (ref "D52") (pin "A") (pinfunction "A_A") (pintype "passive"))
      (node (ref "D58") (pin "A") (pinfunction "A_A") (pintype "passive"))
      (node (ref "D64") (pin "A") (pinfunction "A_A") (pintype "passive"))
      (node (ref "D70") (pin "A") (pinfunction "A_A") (pintype "passive"))
      (node (ref "D76") (pin "A") (pinfunction "A_A") (pintype "passive"))
      (node (ref "D82") (pin "A") (pinfunction "A_A") (pintype "passive"))
      (node (ref "D87") (pin "A") (pinfunction "A_A") (pintype "passive"))
      (node (ref "D91") (pin "A") (pinfunction "A_A") (pintype "passive"))
      (node (ref "U1") (pin "30") (pinfunction "PB6_30") (pintype "bidirectional"))
    )
    (net (code "16") (name "/E3") (class "Default")
      (node (ref "D15") (pin "A") (pinfunction "A_A") (pintype "passive"))
      (node (ref "D21") (pin "A") (pinfunction "A_A") (pintype "passive"))
      (node (ref "D27") (pin "A") (pinfunction "A_A") (pintype "passive"))
      (node (ref "D3") (pin "A") (pinfunction "A_A") (pintype "passive"))
      (node (ref "D33") (pin "A") (pinfunction "A_A") (pintype "passive"))
      (node (ref "D39") (pin "A") (pinfunction "A_A") (pintype "passive"))
      (node (ref "D45") (pin "A") (pinfunction "A_A") (pintype "passive"))
      (node (ref "D51") (pin "A") (pinfunction "A_A") (pintype "passive"))
      (node (ref "D57") (pin "A") (pinfunction "A_A") (pintype "passive"))
      (node (ref "D63") (pin "A") (pinfunction "A_A") (pintype "passive"))
      (node (ref "D69") (pin "A") (pinfunction "A_A") (pintype "passive"))
      (node (ref "D75") (pin "A") (pinfunction "A_A") (pintype "passive"))
      (node (ref "D81") (pin "A") (pinfunction "A_A") (pintype "passive"))
      (node (ref "D9") (pin "A") (pinfunction "A_A") (pintype "passive"))
      (node (ref "U1") (pin "29") (pinfunction "PB5_29") (pintype "bidirectional"))
    )
    (net (code "17") (name "/E4") (class "Default")
      (node (ref "D14") (pin "A") (pinfunction "A_A") (pintype "passive"))
      (node (ref "D2") (pin "A") (pinfunction "A_A") (pintype "passive"))
      (node (ref "D20") (pin "A") (pinfunction "A_A") (pintype "passive"))
      (node (ref "D26") (pin "A") (pinfunction "A_A") (pintype "passive"))
      (node (ref "D32") (pin "A") (pinfunction "A_A") (pintype "passive"))
      (node (ref "D38") (pin "A") (pinfunction "A_A") (pintype "passive"))
      (node (ref "D44") (pin "A") (pinfunction "A_A") (pintype "passive"))
      (node (ref "D50") (pin "A") (pinfunction "A_A") (pintype "passive"))
      (node (ref "D56") (pin "A") (pinfunction "A_A") (pintype "passive"))
      (node (ref "D62") (pin "A") (pinfunction "A_A") (pintype "passive"))
      (node (ref "D68") (pin "A") (pinfunction "A_A") (pintype "passive"))
      (node (ref "D74") (pin "A") (pinfunction "A_A") (pintype "passive"))
      (node (ref "D8") (pin "A") (pinfunction "A_A") (pintype "passive"))
      (node (ref "D80") (pin "A") (pinfunction "A_A") (pintype "passive"))
      (node (ref "D86") (pin "A") (pinfunction "A_A") (pintype "passive"))
      (node (ref "U1") (pin "28") (pinfunction "PB4_28") (pintype "bidirectional"))
    )
    (net (code "18") (name "/E5") (class "Default")
      (node (ref "D1") (pin "A") (pinfunction "A_A") (pintype "passive"))
      (node (ref "D13") (pin "A") (pinfunction "A_A") (pintype "passive"))
      (node (ref "D19") (pin "A") (pinfunction "A_A") (pintype "passive"))
      (node (ref "D25") (pin "A") (pinfunction "A_A") (pintype "passive"))
      (node (ref "D31") (pin "A") (pinfunction "A_A") (pintype "passive"))
      (node (ref "D37") (pin "A") (pinfunction "A_A") (pintype "passive"))
      (node (ref "D43") (pin "A") (pinfunction "A_A") (pintype "passive"))
      (node (ref "D49") (pin "A") (pinfunction "A_A") (pintype "passive"))
      (node (ref "D55") (pin "A") (pinfunction "A_A") (pintype "passive"))
      (node (ref "D61") (pin "A") (pinfunction "A_A") (pintype "passive"))
      (node (ref "D67") (pin "A") (pinfunction "A_A") (pintype "passive"))
      (node (ref "D7") (pin "A") (pinfunction "A_A") (pintype "passive"))
      (node (ref "D73") (pin "A") (pinfunction "A_A") (pintype "passive"))
      (node (ref "D79") (pin "A") (pinfunction "A_A") (pintype "passive"))
      (node (ref "D85") (pin "A") (pinfunction "A_A") (pintype "passive"))
      (node (ref "D90") (pin "A") (pinfunction "A_A") (pintype "passive"))
      (node (ref "U1") (pin "27") (pinfunction "PD7_27") (pintype "bidirectional"))
    )
    (net (code "19") (name "/LEDS") (class "Default")
      (node (ref "LED1") (pin "2") (pinfunction "A_2") (pintype "power_in"))
      (node (ref "LED10") (pin "2") (pinfunction "A_2") (pintype "power_in"))
      (node (ref "LED11") (pin "2") (pinfunction "A_2") (pintype "power_in"))
      (node (ref "LED12") (pin "2") (pinfunction "A_2") (pintype "power_in"))
      (node (ref "LED13") (pin "2") (pinfunction "A_2") (pintype "power_in"))
      (node (ref "LED14") (pin "2") (pinfunction "A_2") (pintype "power_in"))
      (node (ref "LED15") (pin "2") (pinfunction "A_2") (pintype "power_in"))
      (node (ref "LED16") (pin "2") (pinfunction "A_2") (pintype "power_in"))
      (node (ref "LED2") (pin "2") (pinfunction "A_2") (pintype "power_in"))
      (node (ref "LED3") (pin "2") (pinfunction "A_2") (pintype "power_in"))
      (node (ref "LED4") (pin "2") (pinfunction "A_2") (pintype "power_in"))
      (node (ref "LED5") (pin "2") (pinfunction "A_2") (pintype "power_in"))
      (node (ref "LED6") (pin "2") (pinfunction "A_2") (pintype "power_in"))
      (node (ref "LED7") (pin "2") (pinfunction "A_2") (pintype "power_in"))
      (node (ref "LED8") (pin "2") (pinfunction "A_2") (pintype "power_in"))
      (node (ref "LED9") (pin "2") (pinfunction "A_2") (pintype "power_in"))
      (node (ref "LEDSJUMPER") (pin "1") (pinfunction "1_1") (pintype "passive"))
      (node (ref "R3") (pin "1") (pinfunction "1_1") (pintype "passive"))
    )
    (net (code "20") (name "/MISO") (class "Default")
      (node (ref "J3") (pin "5") (pinfunction "5_5") (pintype "passive"))
      (node (ref "U1") (pin "11") (pinfunction "PB3_11") (pintype "bidirectional"))
    )
    (net (code "21") (name "/MOSI") (class "Default")
      (node (ref "J3") (pin "4") (pinfunction "4_4") (pintype "passive"))
      (node (ref "U1") (pin "10") (pinfunction "PB2_10") (pintype "bidirectional"))
    )
    (net (code "22") (name "/MUX0") (class "Default")
      (node (ref "MULTIPLEXOR") (pin "1") (pinfunction "0_1") (pintype "output"))
      (node (ref "U$1") (pin "SW1") (pinfunction "PIN-1_SW1") (pintype "bidirectional"))
      (node (ref "U$2") (pin "SW1") (pinfunction "PIN-1_SW1") (pintype "bidirectional"))
      (node (ref "U$3") (pin "SW1") (pinfunction "PIN-1_SW1") (pintype "bidirectional"))
      (node (ref "U$4") (pin "SW1") (pinfunction "PIN-1_SW1") (pintype "bidirectional"))
      (node (ref "U$5") (pin "SW1") (pinfunction "PIN-1_SW1") (pintype "bidirectional"))
      (node (ref "U$6") (pin "SW1") (pinfunction "PIN-1_SW1") (pintype "bidirectional"))
    )
    (net (code "23") (name "/MUX1") (class "Default")
      (node (ref "DUPLICADO1") (pin "SW1") (pinfunction "PIN-1_SW1") (pintype "bidirectional"))
      (node (ref "MULTIPLEXOR") (pin "2") (pinfunction "1_2") (pintype "output"))
      (node (ref "U$10") (pin "SW1") (pinfunction "PIN-1_SW1") (pintype "bidirectional"))
      (node (ref "U$11") (pin "SW1") (pinfunction "PIN-1_SW1") (pintype "bidirectional"))
      (node (ref "U$12") (pin "SW1") (pinfunction "PIN-1_SW1") (pintype "bidirectional"))
      (node (ref "U$7") (pin "SW1") (pinfunction "PIN-1_SW1") (pintype "bidirectional"))
      (node (ref "U$8") (pin "SW1") (pinfunction "PIN-1_SW1") (pintype "bidirectional"))
      (node (ref "U$9") (pin "SW1") (pinfunction "PIN-1_SW1") (pintype "bidirectional"))
    )
    (net (code "24") (name "/MUX2") (class "Default")
      (node (ref "DUPLICADO2") (pin "SW1") (pinfunction "PIN-1_SW1") (pintype "bidirectional"))
      (node (ref "MULTIPLEXOR") (pin "3") (pinfunction "2_3") (pintype "output"))
      (node (ref "U$13") (pin "SW1") (pinfunction "PIN-1_SW1") (pintype "bidirectional"))
      (node (ref "U$14") (pin "SW1") (pinfunction "PIN-1_SW1") (pintype "bidirectional"))
      (node (ref "U$15") (pin "SW1") (pinfunction "PIN-1_SW1") (pintype "bidirectional"))
      (node (ref "U$16") (pin "SW1") (pinfunction "PIN-1_SW1") (pintype "bidirectional"))
      (node (ref "U$17") (pin "SW1") (pinfunction "PIN-1_SW1") (pintype "bidirectional"))
      (node (ref "U$18") (pin "SW1") (pinfunction "PIN-1_SW1") (pintype "bidirectional"))
    )
    (net (code "25") (name "/MUX3") (class "Default")
      (node (ref "DUPLICADO3") (pin "SW1") (pinfunction "PIN-1_SW1") (pintype "bidirectional"))
      (node (ref "MULTIPLEXOR") (pin "4") (pinfunction "3_4") (pintype "output"))
      (node (ref "U$19") (pin "SW1") (pinfunction "PIN-1_SW1") (pintype "bidirectional"))
      (node (ref "U$20") (pin "SW1") (pinfunction "PIN-1_SW1") (pintype "bidirectional"))
      (node (ref "U$21") (pin "SW1") (pinfunction "PIN-1_SW1") (pintype "bidirectional"))
      (node (ref "U$22") (pin "SW1") (pinfunction "PIN-1_SW1") (pintype "bidirectional"))
      (node (ref "U$23") (pin "SW1") (pinfunction "PIN-1_SW1") (pintype "bidirectional"))
      (node (ref "U$24") (pin "SW1") (pinfunction "PIN-1_SW1") (pintype "bidirectional"))
    )
    (net (code "26") (name "/MUX4") (class "Default")
      (node (ref "DUPLICADO4") (pin "SW1") (pinfunction "PIN-1_SW1") (pintype "bidirectional"))
      (node (ref "MULTIPLEXOR") (pin "5") (pinfunction "4_5") (pintype "output"))
      (node (ref "U$25") (pin "SW1") (pinfunction "PIN-1_SW1") (pintype "bidirectional"))
      (node (ref "U$26") (pin "SW1") (pinfunction "PIN-1_SW1") (pintype "bidirectional"))
      (node (ref "U$27") (pin "SW1") (pinfunction "PIN-1_SW1") (pintype "bidirectional"))
      (node (ref "U$28") (pin "SW1") (pinfunction "PIN-1_SW1") (pintype "bidirectional"))
      (node (ref "U$29") (pin "SW1") (pinfunction "PIN-1_SW1") (pintype "bidirectional"))
      (node (ref "U$30") (pin "SW1") (pinfunction "PIN-1_SW1") (pintype "bidirectional"))
    )
    (net (code "27") (name "/MUX5") (class "Default")
      (node (ref "DUPLICADO5") (pin "SW1") (pinfunction "PIN-1_SW1") (pintype "bidirectional"))
      (node (ref "MULTIPLEXOR") (pin "6") (pinfunction "5_6") (pintype "output"))
      (node (ref "U$31") (pin "SW1") (pinfunction "PIN-1_SW1") (pintype "bidirectional"))
      (node (ref "U$32") (pin "SW1") (pinfunction "PIN-1_SW1") (pintype "bidirectional"))
      (node (ref "U$33") (pin "SW1") (pinfunction "PIN-1_SW1") (pintype "bidirectional"))
      (node (ref "U$34") (pin "SW1") (pinfunction "PIN-1_SW1") (pintype "bidirectional"))
      (node (ref "U$35") (pin "SW1") (pinfunction "PIN-1_SW1") (pintype "bidirectional"))
      (node (ref "U$36") (pin "SW1") (pinfunction "PIN-1_SW1") (pintype "bidirectional"))
    )
    (net (code "28") (name "/MUX6") (class "Default")
      (node (ref "DUPLICADO6") (pin "SW1") (pinfunction "PIN-1_SW1") (pintype "bidirectional"))
      (node (ref "MULTIPLEXOR") (pin "7") (pinfunction "6_7") (pintype "output"))
      (node (ref "U$37") (pin "SW1") (pinfunction "PIN-1_SW1") (pintype "bidirectional"))
      (node (ref "U$38") (pin "SW1") (pinfunction "PIN-1_SW1") (pintype "bidirectional"))
      (node (ref "U$39") (pin "SW1") (pinfunction "PIN-1_SW1") (pintype "bidirectional"))
      (node (ref "U$40") (pin "SW1") (pinfunction "PIN-1_SW1") (pintype "bidirectional"))
      (node (ref "U$41") (pin "SW1") (pinfunction "PIN-1_SW1") (pintype "bidirectional"))
      (node (ref "U$42") (pin "SW1") (pinfunction "PIN-1_SW1") (pintype "bidirectional"))
    )
    (net (code "29") (name "/MUX7") (class "Default")
      (node (ref "DUPLICADO7") (pin "SW1") (pinfunction "PIN-1_SW1") (pintype "bidirectional"))
      (node (ref "MULTIPLEXOR") (pin "8") (pinfunction "7_8") (pintype "output"))
      (node (ref "U$43") (pin "SW1") (pinfunction "PIN-1_SW1") (pintype "bidirectional"))
      (node (ref "U$44") (pin "SW1") (pinfunction "PIN-1_SW1") (pintype "bidirectional"))
      (node (ref "U$45") (pin "SW1") (pinfunction "PIN-1_SW1") (pintype "bidirectional"))
      (node (ref "U$46") (pin "SW1") (pinfunction "PIN-1_SW1") (pintype "bidirectional"))
      (node (ref "U$47") (pin "SW1") (pinfunction "PIN-1_SW1") (pintype "bidirectional"))
      (node (ref "U$48") (pin "SW1") (pinfunction "PIN-1_SW1") (pintype "bidirectional"))
    )
    (net (code "30") (name "/MUX8") (class "Default")
      (node (ref "DUPLICADO8") (pin "SW1") (pinfunction "PIN-1_SW1") (pintype "bidirectional"))
      (node (ref "MULTIPLEXOR") (pin "9") (pinfunction "8_9") (pintype "output"))
      (node (ref "U$49") (pin "SW1") (pinfunction "PIN-1_SW1") (pintype "bidirectional"))
      (node (ref "U$50") (pin "SW1") (pinfunction "PIN-1_SW1") (pintype "bidirectional"))
      (node (ref "U$51") (pin "SW1") (pinfunction "PIN-1_SW1") (pintype "bidirectional"))
      (node (ref "U$52") (pin "SW1") (pinfunction "PIN-1_SW1") (pintype "bidirectional"))
      (node (ref "U$53") (pin "SW1") (pinfunction "PIN-1_SW1") (pintype "bidirectional"))
      (node (ref "U$54") (pin "SW1") (pinfunction "PIN-1_SW1") (pintype "bidirectional"))
    )
    (net (code "31") (name "/MUX9") (class "Default")
      (node (ref "DUPLICADO9") (pin "SW1") (pinfunction "PIN-1_SW1") (pintype "bidirectional"))
      (node (ref "MULTIPLEXOR") (pin "10") (pinfunction "9_10") (pintype "output"))
      (node (ref "U$55") (pin "SW1") (pinfunction "PIN-1_SW1") (pintype "bidirectional"))
      (node (ref "U$56") (pin "SW1") (pinfunction "PIN-1_SW1") (pintype "bidirectional"))
      (node (ref "U$57") (pin "SW1") (pinfunction "PIN-1_SW1") (pintype "bidirectional"))
      (node (ref "U$58") (pin "SW1") (pinfunction "PIN-1_SW1") (pintype "bidirectional"))
      (node (ref "U$59") (pin "SW1") (pinfunction "PIN-1_SW1") (pintype "bidirectional"))
      (node (ref "U$60") (pin "SW1") (pinfunction "PIN-1_SW1") (pintype "bidirectional"))
    )
    (net (code "32") (name "/MUX10") (class "Default")
      (node (ref "DUPLICADO10") (pin "SW1") (pinfunction "PIN-1_SW1") (pintype "bidirectional"))
      (node (ref "MULTIPLEXOR") (pin "11") (pinfunction "10_11") (pintype "output"))
      (node (ref "PUNTODUPLICADO") (pin "SW1") (pinfunction "PIN-1_SW1") (pintype "bidirectional"))
      (node (ref "U$61") (pin "SW1") (pinfunction "PIN-1_SW1") (pintype "bidirectional"))
      (node (ref "U$62") (pin "SW1") (pinfunction "PIN-1_SW1") (pintype "bidirectional"))
      (node (ref "U$63") (pin "SW1") (pinfunction "PIN-1_SW1") (pintype "bidirectional"))
      (node (ref "U$64") (pin "SW1") (pinfunction "PIN-1_SW1") (pintype "bidirectional"))
      (node (ref "U$65") (pin "SW1") (pinfunction "PIN-1_SW1") (pintype "bidirectional"))
      (node (ref "U$66") (pin "SW1") (pinfunction "PIN-1_SW1") (pintype "bidirectional"))
    )
    (net (code "33") (name "/MUX11") (class "Default")
      (node (ref "MULTIPLEXOR") (pin "13") (pinfunction "11_13") (pintype "output"))
      (node (ref "U$67") (pin "SW1") (pinfunction "PIN-1_SW1") (pintype "bidirectional"))
      (node (ref "U$68") (pin "SW1") (pinfunction "PIN-1_SW1") (pintype "bidirectional"))
      (node (ref "U$69") (pin "SW1") (pinfunction "PIN-1_SW1") (pintype "bidirectional"))
      (node (ref "U$70") (pin "SW1") (pinfunction "PIN-1_SW1") (pintype "bidirectional"))
      (node (ref "U$71") (pin "SW1") (pinfunction "PIN-1_SW1") (pintype "bidirectional"))
      (node (ref "U$72") (pin "SW1") (pinfunction "PIN-1_SW1") (pintype "bidirectional"))
    )
    (net (code "34") (name "/MUX12") (class "Default")
      (node (ref "MULTIPLEXOR") (pin "14") (pinfunction "12_14") (pintype "output"))
      (node (ref "U$73") (pin "SW1") (pinfunction "PIN-1_SW1") (pintype "bidirectional"))
      (node (ref "U$74") (pin "SW1") (pinfunction "PIN-1_SW1") (pintype "bidirectional"))
      (node (ref "U$75") (pin "SW1") (pinfunction "PIN-1_SW1") (pintype "bidirectional"))
      (node (ref "U$76") (pin "SW1") (pinfunction "PIN-1_SW1") (pintype "bidirectional"))
      (node (ref "U$77") (pin "SW1") (pinfunction "PIN-1_SW1") (pintype "bidirectional"))
      (node (ref "U$78") (pin "SW1") (pinfunction "PIN-1_SW1") (pintype "bidirectional"))
    )
    (net (code "35") (name "/MUX13") (class "Default")
      (node (ref "ENTERDUPLICADO") (pin "SW1") (pinfunction "PIN-1_SW1") (pintype "bidirectional"))
      (node (ref "MULTIPLEXOR") (pin "15") (pinfunction "13_15") (pintype "output"))
      (node (ref "U$79") (pin "SW1") (pinfunction "PIN-1_SW1") (pintype "bidirectional"))
      (node (ref "U$80") (pin "SW1") (pinfunction "PIN-1_SW1") (pintype "bidirectional"))
      (node (ref "U$81") (pin "SW1") (pinfunction "PIN-1_SW1") (pintype "bidirectional"))
      (node (ref "U$82") (pin "SW1") (pinfunction "PIN-1_SW1") (pintype "bidirectional"))
      (node (ref "U$83") (pin "SW1") (pinfunction "PIN-1_SW1") (pintype "bidirectional"))
      (node (ref "U$84") (pin "SW1") (pinfunction "PIN-1_SW1") (pintype "bidirectional"))
    )
    (net (code "36") (name "/MUX14") (class "Default")
      (node (ref "MULTIPLEXOR") (pin "16") (pinfunction "14_16") (pintype "output"))
      (node (ref "U$85") (pin "SW1") (pinfunction "PIN-1_SW1") (pintype "bidirectional"))
      (node (ref "U$86") (pin "SW1") (pinfunction "PIN-1_SW1") (pintype "bidirectional"))
      (node (ref "U$87") (pin "SW1") (pinfunction "PIN-1_SW1") (pintype "bidirectional"))
      (node (ref "U$88") (pin "SW1") (pinfunction "PIN-1_SW1") (pintype "bidirectional"))
      (node (ref "U$89") (pin "SW1") (pinfunction "PIN-1_SW1") (pintype "bidirectional"))
    )
    (net (code "37") (name "/MUX15") (class "Default")
      (node (ref "MULTIPLEXOR") (pin "17") (pinfunction "15_17") (pintype "output"))
      (node (ref "U$90") (pin "SW1") (pinfunction "PIN-1_SW1") (pintype "bidirectional"))
      (node (ref "U$91") (pin "SW1") (pinfunction "PIN-1_SW1") (pintype "bidirectional"))
      (node (ref "U$92") (pin "SW1") (pinfunction "PIN-1_SW1") (pintype "bidirectional"))
      (node (ref "U$93") (pin "SW1") (pinfunction "PIN-1_SW1") (pintype "bidirectional"))
    )
    (net (code "38") (name "/ONOFF") (class "Default")
      (node (ref "LEDSJUMPER") (pin "2") (pinfunction "2_2") (pintype "passive"))
      (node (ref "ONOFF") (pin "1") (pinfunction "1_1") (pintype "passive"))
      (node (ref "R3") (pin "2") (pinfunction "2_2") (pintype "passive"))
    )
    (net (code "39") (name "/RESET") (class "Default")
      (node (ref "BUTTON") (pin "4") (pinfunction "P1_4") (pintype "passive"))
      (node (ref "J3") (pin "3") (pinfunction "3_3") (pintype "passive"))
      (node (ref "R5") (pin "2") (pinfunction "2_2") (pintype "passive"))
      (node (ref "U1") (pin "13") (pinfunction "~{RESET}_13") (pintype "input"))
    )
    (net (code "40") (name "/RX") (class "Default")
      (node (ref "RXTX") (pin "1") (pinfunction "1_1") (pintype "passive"))
      (node (ref "U1") (pin "20") (pinfunction "PD2_20") (pintype "bidirectional"))
    )
    (net (code "41") (name "/SCK") (class "Default")
      (node (ref "J3") (pin "6") (pinfunction "6_6") (pintype "passive"))
      (node (ref "U1") (pin "9") (pinfunction "PB1_9") (pintype "bidirectional"))
    )
    (net (code "42") (name "/SCL") (class "Default")
      (node (ref "SD") (pin "2") (pinfunction "2_2") (pintype "passive"))
      (node (ref "U1") (pin "18") (pinfunction "PD0_18") (pintype "bidirectional"))
    )
    (net (code "43") (name "/SDA") (class "Default")
      (node (ref "SD") (pin "1") (pinfunction "1_1") (pintype "passive"))
      (node (ref "U1") (pin "19") (pinfunction "PD1_19") (pintype "bidirectional"))
    )
    (net (code "44") (name "/TX") (class "Default")
      (node (ref "RXTX") (pin "2") (pinfunction "2_2") (pintype "passive"))
      (node (ref "U1") (pin "21") (pinfunction "PD3_21") (pintype "bidirectional"))
    )
    (net (code "45") (name "GND") (class "Default")
      (node (ref "BUTTON") (pin "1") (pinfunction "S_1") (pintype "passive"))
      (node (ref "C1-0.1U") (pin "2") (pinfunction "2_2") (pintype "passive"))
      (node (ref "C1-1UF1") (pin "2") (pinfunction "2_2") (pintype "passive"))
      (node (ref "C1-1UF2") (pin "2") (pinfunction "2_2") (pintype "passive"))
      (node (ref "C1-22PF1") (pin "2") (pinfunction "2_2") (pintype "passive"))
      (node (ref "C1-22PF2") (pin "2") (pinfunction "2_2") (pintype "passive"))
      (node (ref "C2-0.1U") (pin "2") (pinfunction "2_2") (pintype "passive"))
      (node (ref "C3-0.1U") (pin "2") (pinfunction "2_2") (pintype "passive"))
      (node (ref "J3") (pin "1") (pinfunction "1_1") (pintype "passive"))
      (node (ref "LED1") (pin "1") (pinfunction "K_1") (pintype "power_in"))
      (node (ref "LED10") (pin "1") (pinfunction "K_1") (pintype "power_in"))
      (node (ref "LED11") (pin "1") (pinfunction "K_1") (pintype "power_in"))
      (node (ref "LED12") (pin "1") (pinfunction "K_1") (pintype "power_in"))
      (node (ref "LED13") (pin "1") (pinfunction "K_1") (pintype "power_in"))
      (node (ref "LED14") (pin "1") (pinfunction "K_1") (pintype "power_in"))
      (node (ref "LED15") (pin "1") (pinfunction "K_1") (pintype "power_in"))
      (node (ref "LED16") (pin "1") (pinfunction "K_1") (pintype "power_in"))
      (node (ref "LED2") (pin "1") (pinfunction "K_1") (pintype "power_in"))
      (node (ref "LED3") (pin "1") (pinfunction "K_1") (pintype "power_in"))
      (node (ref "LED4") (pin "1") (pinfunction "K_1") (pintype "power_in"))
      (node (ref "LED5") (pin "1") (pinfunction "K_1") (pintype "power_in"))
      (node (ref "LED6") (pin "1") (pinfunction "K_1") (pintype "power_in"))
      (node (ref "LED7") (pin "1") (pinfunction "K_1") (pintype "power_in"))
      (node (ref "LED8") (pin "1") (pinfunction "K_1") (pintype "power_in"))
      (node (ref "LED9") (pin "1") (pinfunction "K_1") (pintype "power_in"))
      (node (ref "MULTIPLEXOR") (pin "12") (pinfunction "-UB_12") (pintype "power_in"))
      (node (ref "MULTIPLEXOR") (pin "18") (pinfunction "~{G1}_18") (pintype "input"))
      (node (ref "MULTIPLEXOR") (pin "19") (pinfunction "~{G2}_19") (pintype "input"))
      (node (ref "R4") (pin "1") (pinfunction "1_1") (pintype "passive"))
      (node (ref "U1") (pin "15") (pinfunction "GND_15") (pintype "power_in"))
      (node (ref "U1") (pin "23") (pinfunction "GND_23") (pintype "power_in"))
      (node (ref "U1") (pin "35") (pinfunction "GND_35") (pintype "power_in"))
      (node (ref "U1") (pin "43") (pinfunction "GND_43") (pintype "power_in"))
      (node (ref "U1") (pin "5") (pinfunction "UGND_5") (pintype "power_in"))
      (node (ref "X2") (pin "GND") (pinfunction "GND_GND") (pintype "bidirectional"))
    )
    (net (code "46") (name "Net-(DUPLICADO1-PIN-2)") (class "Default")
      (node (ref "D11") (pin "C") (pinfunction "C_C") (pintype "passive"))
      (node (ref "DUPLICADO1") (pin "SW2") (pinfunction "PIN-2_SW2") (pintype "bidirectional"))
      (node (ref "U$11") (pin "SW2") (pinfunction "PIN-2_SW2") (pintype "bidirectional"))
    )
    (net (code "47") (name "Net-(DUPLICADO2-PIN-2)") (class "Default")
      (node (ref "D17") (pin "C") (pinfunction "C_C") (pintype "passive"))
      (node (ref "DUPLICADO2") (pin "SW2") (pinfunction "PIN-2_SW2") (pintype "bidirectional"))
      (node (ref "U$17") (pin "SW2") (pinfunction "PIN-2_SW2") (pintype "bidirectional"))
    )
    (net (code "48") (name "Net-(DUPLICADO3-PIN-2)") (class "Default")
      (node (ref "D23") (pin "C") (pinfunction "C_C") (pintype "passive"))
      (node (ref "DUPLICADO3") (pin "SW2") (pinfunction "PIN-2_SW2") (pintype "bidirectional"))
      (node (ref "U$23") (pin "SW2") (pinfunction "PIN-2_SW2") (pintype "bidirectional"))
    )
    (net (code "49") (name "Net-(DUPLICADO4-PIN-2)") (class "Default")
      (node (ref "D29") (pin "C") (pinfunction "C_C") (pintype "passive"))
      (node (ref "DUPLICADO4") (pin "SW2") (pinfunction "PIN-2_SW2") (pintype "bidirectional"))
      (node (ref "U$29") (pin "SW2") (pinfunction "PIN-2_SW2") (pintype "bidirectional"))
    )
    (net (code "50") (name "Net-(DUPLICADO5-PIN-2)") (class "Default")
      (node (ref "D35") (pin "C") (pinfunction "C_C") (pintype "passive"))
      (node (ref "DUPLICADO5") (pin "SW2") (pinfunction "PIN-2_SW2") (pintype "bidirectional"))
      (node (ref "U$35") (pin "SW2") (pinfunction "PIN-2_SW2") (pintype "bidirectional"))
    )
    (net (code "51") (name "Net-(DUPLICADO6-PIN-2)") (class "Default")
      (node (ref "D41") (pin "C") (pinfunction "C_C") (pintype "passive"))
      (node (ref "DUPLICADO6") (pin "SW2") (pinfunction "PIN-2_SW2") (pintype "bidirectional"))
      (node (ref "U$41") (pin "SW2") (pinfunction "PIN-2_SW2") (pintype "bidirectional"))
    )
    (net (code "52") (name "Net-(DUPLICADO7-PIN-2)") (class "Default")
      (node (ref "D47") (pin "C") (pinfunction "C_C") (pintype "passive"))
      (node (ref "DUPLICADO7") (pin "SW2") (pinfunction "PIN-2_SW2") (pintype "bidirectional"))
      (node (ref "U$47") (pin "SW2") (pinfunction "PIN-2_SW2") (pintype "bidirectional"))
    )
    (net (code "53") (name "Net-(DUPLICADO8-PIN-2)") (class "Default")
      (node (ref "D53") (pin "C") (pinfunction "C_C") (pintype "passive"))
      (node (ref "DUPLICADO8") (pin "SW2") (pinfunction "PIN-2_SW2") (pintype "bidirectional"))
      (node (ref "U$53") (pin "SW2") (pinfunction "PIN-2_SW2") (pintype "bidirectional"))
    )
    (net (code "54") (name "Net-(DUPLICADO9-PIN-2)") (class "Default")
      (node (ref "D59") (pin "C") (pinfunction "C_C") (pintype "passive"))
      (node (ref "DUPLICADO9") (pin "SW2") (pinfunction "PIN-2_SW2") (pintype "bidirectional"))
      (node (ref "U$59") (pin "SW2") (pinfunction "PIN-2_SW2") (pintype "bidirectional"))
    )
    (net (code "55") (name "Net-(DUPLICADO10-PIN-2)") (class "Default")
      (node (ref "D65") (pin "C") (pinfunction "C_C") (pintype "passive"))
      (node (ref "DUPLICADO10") (pin "SW2") (pinfunction "PIN-2_SW2") (pintype "bidirectional"))
      (node (ref "U$65") (pin "SW2") (pinfunction "PIN-2_SW2") (pintype "bidirectional"))
    )
    (net (code "56") (name "Net-(ENTERDUPLICADO-PIN-2)") (class "Default")
      (node (ref "D82") (pin "C") (pinfunction "C_C") (pintype "passive"))
      (node (ref "ENTERDUPLICADO") (pin "SW2") (pinfunction "PIN-2_SW2") (pintype "bidirectional"))
      (node (ref "U$82") (pin "SW2") (pinfunction "PIN-2_SW2") (pintype "bidirectional"))
    )
    (net (code "57") (name "Net-(PUNTODUPLICADO-PIN-2)") (class "Default")
      (node (ref "D62") (pin "C") (pinfunction "C_C") (pintype "passive"))
      (node (ref "PUNTODUPLICADO") (pin "SW2") (pinfunction "PIN-2_SW2") (pintype "bidirectional"))
      (node (ref "U$62") (pin "SW2") (pinfunction "PIN-2_SW2") (pintype "bidirectional"))
    )
    (net (code "58") (name "Net-(U$1-PIN-2)") (class "Default")
      (node (ref "D1") (pin "C") (pinfunction "C_C") (pintype "passive"))
      (node (ref "U$1") (pin "SW2") (pinfunction "PIN-2_SW2") (pintype "bidirectional"))
    )
    (net (code "59") (name "Net-(U$2-PIN-2)") (class "Default")
      (node (ref "D2") (pin "C") (pinfunction "C_C") (pintype "passive"))
      (node (ref "U$2") (pin "SW2") (pinfunction "PIN-2_SW2") (pintype "bidirectional"))
    )
    (net (code "60") (name "Net-(U$3-PIN-2)") (class "Default")
      (node (ref "D3") (pin "C") (pinfunction "C_C") (pintype "passive"))
      (node (ref "U$3") (pin "SW2") (pinfunction "PIN-2_SW2") (pintype "bidirectional"))
    )
    (net (code "61") (name "Net-(U$4-PIN-2)") (class "Default")
      (node (ref "D4") (pin "C") (pinfunction "C_C") (pintype "passive"))
      (node (ref "U$4") (pin "SW2") (pinfunction "PIN-2_SW2") (pintype "bidirectional"))
    )
    (net (code "62") (name "Net-(U$5-PIN-2)") (class "Default")
      (node (ref "D5") (pin "C") (pinfunction "C_C") (pintype "passive"))
      (node (ref "U$5") (pin "SW2") (pinfunction "PIN-2_SW2") (pintype "bidirectional"))
    )
    (net (code "63") (name "Net-(U$6-PIN-2)") (class "Default")
      (node (ref "D6") (pin "C") (pinfunction "C_C") (pintype "passive"))
      (node (ref "U$6") (pin "SW2") (pinfunction "PIN-2_SW2") (pintype "bidirectional"))
    )
    (net (code "64") (name "Net-(U$7-PIN-2)") (class "Default")
      (node (ref "D7") (pin "C") (pinfunction "C_C") (pintype "passive"))
      (node (ref "U$7") (pin "SW2") (pinfunction "PIN-2_SW2") (pintype "bidirectional"))
    )
    (net (code "65") (name "Net-(U$8-PIN-2)") (class "Default")
      (node (ref "D8") (pin "C") (pinfunction "C_C") (pintype "passive"))
      (node (ref "U$8") (pin "SW2") (pinfunction "PIN-2_SW2") (pintype "bidirectional"))
    )
    (net (code "66") (name "Net-(U$9-PIN-2)") (class "Default")
      (node (ref "D9") (pin "C") (pinfunction "C_C") (pintype "passive"))
      (node (ref "U$9") (pin "SW2") (pinfunction "PIN-2_SW2") (pintype "bidirectional"))
    )
    (net (code "67") (name "Net-(U$10-PIN-2)") (class "Default")
      (node (ref "D10") (pin "C") (pinfunction "C_C") (pintype "passive"))
      (node (ref "U$10") (pin "SW2") (pinfunction "PIN-2_SW2") (pintype "bidirectional"))
    )
    (net (code "68") (name "Net-(U$12-PIN-2)") (class "Default")
      (node (ref "D12") (pin "C") (pinfunction "C_C") (pintype "passive"))
      (node (ref "U$12") (pin "SW2") (pinfunction "PIN-2_SW2") (pintype "bidirectional"))
    )
    (net (code "69") (name "Net-(U$13-PIN-2)") (class "Default")
      (node (ref "D13") (pin "C") (pinfunction "C_C") (pintype "passive"))
      (node (ref "U$13") (pin "SW2") (pinfunction "PIN-2_SW2") (pintype "bidirectional"))
    )
    (net (code "70") (name "Net-(U$14-PIN-2)") (class "Default")
      (node (ref "D14") (pin "C") (pinfunction "C_C") (pintype "passive"))
      (node (ref "U$14") (pin "SW2") (pinfunction "PIN-2_SW2") (pintype "bidirectional"))
    )
    (net (code "71") (name "Net-(U$15-PIN-2)") (class "Default")
      (node (ref "D15") (pin "C") (pinfunction "C_C") (pintype "passive"))
      (node (ref "U$15") (pin "SW2") (pinfunction "PIN-2_SW2") (pintype "bidirectional"))
    )
    (net (code "72") (name "Net-(U$16-PIN-2)") (class "Default")
      (node (ref "D16") (pin "C") (pinfunction "C_C") (pintype "passive"))
      (node (ref "U$16") (pin "SW2") (pinfunction "PIN-2_SW2") (pintype "bidirectional"))
    )
    (net (code "73") (name "Net-(U$18-PIN-2)") (class "Default")
      (node (ref "D18") (pin "C") (pinfunction "C_C") (pintype "passive"))
      (node (ref "U$18") (pin "SW2") (pinfunction "PIN-2_SW2") (pintype "bidirectional"))
    )
    (net (code "74") (name "Net-(U$19-PIN-2)") (class "Default")
      (node (ref "D19") (pin "C") (pinfunction "C_C") (pintype "passive"))
      (node (ref "U$19") (pin "SW2") (pinfunction "PIN-2_SW2") (pintype "bidirectional"))
    )
    (net (code "75") (name "Net-(U$20-PIN-2)") (class "Default")
      (node (ref "D20") (pin "C") (pinfunction "C_C") (pintype "passive"))
      (node (ref "U$20") (pin "SW2") (pinfunction "PIN-2_SW2") (pintype "bidirectional"))
    )
    (net (code "76") (name "Net-(U$21-PIN-2)") (class "Default")
      (node (ref "D21") (pin "C") (pinfunction "C_C") (pintype "passive"))
      (node (ref "U$21") (pin "SW2") (pinfunction "PIN-2_SW2") (pintype "bidirectional"))
    )
    (net (code "77") (name "Net-(U$22-PIN-2)") (class "Default")
      (node (ref "D22") (pin "C") (pinfunction "C_C") (pintype "passive"))
      (node (ref "U$22") (pin "SW2") (pinfunction "PIN-2_SW2") (pintype "bidirectional"))
    )
    (net (code "78") (name "Net-(U$24-PIN-2)") (class "Default")
      (node (ref "D24") (pin "C") (pinfunction "C_C") (pintype "passive"))
      (node (ref "U$24") (pin "SW2") (pinfunction "PIN-2_SW2") (pintype "bidirectional"))
    )
    (net (code "79") (name "Net-(U$25-PIN-2)") (class "Default")
      (node (ref "D25") (pin "C") (pinfunction "C_C") (pintype "passive"))
      (node (ref "U$25") (pin "SW2") (pinfunction "PIN-2_SW2") (pintype "bidirectional"))
    )
    (net (code "80") (name "Net-(U$26-PIN-2)") (class "Default")
      (node (ref "D26") (pin "C") (pinfunction "C_C") (pintype "passive"))
      (node (ref "U$26") (pin "SW2") (pinfunction "PIN-2_SW2") (pintype "bidirectional"))
    )
    (net (code "81") (name "Net-(U$27-PIN-2)") (class "Default")
      (node (ref "D27") (pin "C") (pinfunction "C_C") (pintype "passive"))
      (node (ref "U$27") (pin "SW2") (pinfunction "PIN-2_SW2") (pintype "bidirectional"))
    )
    (net (code "82") (name "Net-(U$28-PIN-2)") (class "Default")
      (node (ref "D28") (pin "C") (pinfunction "C_C") (pintype "passive"))
      (node (ref "U$28") (pin "SW2") (pinfunction "PIN-2_SW2") (pintype "bidirectional"))
    )
    (net (code "83") (name "Net-(U$30-PIN-2)") (class "Default")
      (node (ref "D30") (pin "C") (pinfunction "C_C") (pintype "passive"))
      (node (ref "U$30") (pin "SW2") (pinfunction "PIN-2_SW2") (pintype "bidirectional"))
    )
    (net (code "84") (name "Net-(U$31-PIN-2)") (class "Default")
      (node (ref "D31") (pin "C") (pinfunction "C_C") (pintype "passive"))
      (node (ref "U$31") (pin "SW2") (pinfunction "PIN-2_SW2") (pintype "bidirectional"))
    )
    (net (code "85") (name "Net-(U$32-PIN-2)") (class "Default")
      (node (ref "D32") (pin "C") (pinfunction "C_C") (pintype "passive"))
      (node (ref "U$32") (pin "SW2") (pinfunction "PIN-2_SW2") (pintype "bidirectional"))
    )
    (net (code "86") (name "Net-(U$33-PIN-2)") (class "Default")
      (node (ref "D33") (pin "C") (pinfunction "C_C") (pintype "passive"))
      (node (ref "U$33") (pin "SW2") (pinfunction "PIN-2_SW2") (pintype "bidirectional"))
    )
    (net (code "87") (name "Net-(U$34-PIN-2)") (class "Default")
      (node (ref "D34") (pin "C") (pinfunction "C_C") (pintype "passive"))
      (node (ref "U$34") (pin "SW2") (pinfunction "PIN-2_SW2") (pintype "bidirectional"))
    )
    (net (code "88") (name "Net-(U$36-PIN-2)") (class "Default")
      (node (ref "D36") (pin "C") (pinfunction "C_C") (pintype "passive"))
      (node (ref "U$36") (pin "SW2") (pinfunction "PIN-2_SW2") (pintype "bidirectional"))
    )
    (net (code "89") (name "Net-(U$37-PIN-2)") (class "Default")
      (node (ref "D37") (pin "C") (pinfunction "C_C") (pintype "passive"))
      (node (ref "U$37") (pin "SW2") (pinfunction "PIN-2_SW2") (pintype "bidirectional"))
    )
    (net (code "90") (name "Net-(U$38-PIN-2)") (class "Default")
      (node (ref "D38") (pin "C") (pinfunction "C_C") (pintype "passive"))
      (node (ref "U$38") (pin "SW2") (pinfunction "PIN-2_SW2") (pintype "bidirectional"))
    )
    (net (code "91") (name "Net-(U$39-PIN-2)") (class "Default")
      (node (ref "D39") (pin "C") (pinfunction "C_C") (pintype "passive"))
      (node (ref "U$39") (pin "SW2") (pinfunction "PIN-2_SW2") (pintype "bidirectional"))
    )
    (net (code "92") (name "Net-(U$40-PIN-2)") (class "Default")
      (node (ref "D40") (pin "C") (pinfunction "C_C") (pintype "passive"))
      (node (ref "U$40") (pin "SW2") (pinfunction "PIN-2_SW2") (pintype "bidirectional"))
    )
    (net (code "93") (name "Net-(U$42-PIN-2)") (class "Default")
      (node (ref "D42") (pin "C") (pinfunction "C_C") (pintype "passive"))
      (node (ref "U$42") (pin "SW2") (pinfunction "PIN-2_SW2") (pintype "bidirectional"))
    )
    (net (code "94") (name "Net-(U$43-PIN-2)") (class "Default")
      (node (ref "D43") (pin "C") (pinfunction "C_C") (pintype "passive"))
      (node (ref "U$43") (pin "SW2") (pinfunction "PIN-2_SW2") (pintype "bidirectional"))
    )
    (net (code "95") (name "Net-(U$44-PIN-2)") (class "Default")
      (node (ref "D44") (pin "C") (pinfunction "C_C") (pintype "passive"))
      (node (ref "U$44") (pin "SW2") (pinfunction "PIN-2_SW2") (pintype "bidirectional"))
    )
    (net (code "96") (name "Net-(U$45-PIN-2)") (class "Default")
      (node (ref "D45") (pin "C") (pinfunction "C_C") (pintype "passive"))
      (node (ref "U$45") (pin "SW2") (pinfunction "PIN-2_SW2") (pintype "bidirectional"))
    )
    (net (code "97") (name "Net-(U$46-PIN-2)") (class "Default")
      (node (ref "D46") (pin "C") (pinfunction "C_C") (pintype "passive"))
      (node (ref "U$46") (pin "SW2") (pinfunction "PIN-2_SW2") (pintype "bidirectional"))
    )
    (net (code "98") (name "Net-(U$48-PIN-2)") (class "Default")
      (node (ref "D48") (pin "C") (pinfunction "C_C") (pintype "passive"))
      (node (ref "U$48") (pin "SW2") (pinfunction "PIN-2_SW2") (pintype "bidirectional"))
    )
    (net (code "99") (name "Net-(U$49-PIN-2)") (class "Default")
      (node (ref "D49") (pin "C") (pinfunction "C_C") (pintype "passive"))
      (node (ref "U$49") (pin "SW2") (pinfunction "PIN-2_SW2") (pintype "bidirectional"))
    )
    (net (code "100") (name "Net-(U$50-PIN-2)") (class "Default")
      (node (ref "D50") (pin "C") (pinfunction "C_C") (pintype "passive"))
      (node (ref "U$50") (pin "SW2") (pinfunction "PIN-2_SW2") (pintype "bidirectional"))
    )
    (net (code "101") (name "Net-(U$51-PIN-2)") (class "Default")
      (node (ref "D51") (pin "C") (pinfunction "C_C") (pintype "passive"))
      (node (ref "U$51") (pin "SW2") (pinfunction "PIN-2_SW2") (pintype "bidirectional"))
    )
    (net (code "102") (name "Net-(U$52-PIN-2)") (class "Default")
      (node (ref "D52") (pin "C") (pinfunction "C_C") (pintype "passive"))
      (node (ref "U$52") (pin "SW2") (pinfunction "PIN-2_SW2") (pintype "bidirectional"))
    )
    (net (code "103") (name "Net-(U$54-PIN-2)") (class "Default")
      (node (ref "D54") (pin "C") (pinfunction "C_C") (pintype "passive"))
      (node (ref "U$54") (pin "SW2") (pinfunction "PIN-2_SW2") (pintype "bidirectional"))
    )
    (net (code "104") (name "Net-(U$55-PIN-2)") (class "Default")
      (node (ref "D55") (pin "C") (pinfunction "C_C") (pintype "passive"))
      (node (ref "U$55") (pin "SW2") (pinfunction "PIN-2_SW2") (pintype "bidirectional"))
    )
    (net (code "105") (name "Net-(U$56-PIN-2)") (class "Default")
      (node (ref "D56") (pin "C") (pinfunction "C_C") (pintype "passive"))
      (node (ref "U$56") (pin "SW2") (pinfunction "PIN-2_SW2") (pintype "bidirectional"))
    )
    (net (code "106") (name "Net-(U$57-PIN-2)") (class "Default")
      (node (ref "D57") (pin "C") (pinfunction "C_C") (pintype "passive"))
      (node (ref "U$57") (pin "SW2") (pinfunction "PIN-2_SW2") (pintype "bidirectional"))
    )
    (net (code "107") (name "Net-(U$58-PIN-2)") (class "Default")
      (node (ref "D58") (pin "C") (pinfunction "C_C") (pintype "passive"))
      (node (ref "U$58") (pin "SW2") (pinfunction "PIN-2_SW2") (pintype "bidirectional"))
    )
    (net (code "108") (name "Net-(U$60-PIN-2)") (class "Default")
      (node (ref "D60") (pin "C") (pinfunction "C_C") (pintype "passive"))
      (node (ref "U$60") (pin "SW2") (pinfunction "PIN-2_SW2") (pintype "bidirectional"))
    )
    (net (code "109") (name "Net-(U$61-PIN-2)") (class "Default")
      (node (ref "D61") (pin "C") (pinfunction "C_C") (pintype "passive"))
      (node (ref "U$61") (pin "SW2") (pinfunction "PIN-2_SW2") (pintype "bidirectional"))
    )
    (net (code "110") (name "Net-(U$63-PIN-2)") (class "Default")
      (node (ref "D63") (pin "C") (pinfunction "C_C") (pintype "passive"))
      (node (ref "U$63") (pin "SW2") (pinfunction "PIN-2_SW2") (pintype "bidirectional"))
    )
    (net (code "111") (name "Net-(U$64-PIN-2)") (class "Default")
      (node (ref "D64") (pin "C") (pinfunction "C_C") (pintype "passive"))
      (node (ref "U$64") (pin "SW2") (pinfunction "PIN-2_SW2") (pintype "bidirectional"))
    )
    (net (code "112") (name "Net-(U$66-PIN-2)") (class "Default")
      (node (ref "D66") (pin "C") (pinfunction "C_C") (pintype "passive"))
      (node (ref "U$66") (pin "SW2") (pinfunction "PIN-2_SW2") (pintype "bidirectional"))
    )
    (net (code "113") (name "Net-(U$67-PIN-2)") (class "Default")
      (node (ref "D67") (pin "C") (pinfunction "C_C") (pintype "passive"))
      (node (ref "U$67") (pin "SW2") (pinfunction "PIN-2_SW2") (pintype "bidirectional"))
    )
    (net (code "114") (name "Net-(U$68-PIN-2)") (class "Default")
      (node (ref "D68") (pin "C") (pinfunction "C_C") (pintype "passive"))
      (node (ref "U$68") (pin "SW2") (pinfunction "PIN-2_SW2") (pintype "bidirectional"))
    )
    (net (code "115") (name "Net-(U$69-PIN-2)") (class "Default")
      (node (ref "D69") (pin "C") (pinfunction "C_C") (pintype "passive"))
      (node (ref "U$69") (pin "SW2") (pinfunction "PIN-2_SW2") (pintype "bidirectional"))
    )
    (net (code "116") (name "Net-(U$70-PIN-2)") (class "Default")
      (node (ref "D70") (pin "C") (pinfunction "C_C") (pintype "passive"))
      (node (ref "U$70") (pin "SW2") (pinfunction "PIN-2_SW2") (pintype "bidirectional"))
    )
    (net (code "117") (name "Net-(U$71-PIN-2)") (class "Default")
      (node (ref "D71") (pin "C") (pinfunction "C_C") (pintype "passive"))
      (node (ref "U$71") (pin "SW2") (pinfunction "PIN-2_SW2") (pintype "bidirectional"))
    )
    (net (code "118") (name "Net-(U$72-PIN-2)") (class "Default")
      (node (ref "D72") (pin "C") (pinfunction "C_C") (pintype "passive"))
      (node (ref "U$72") (pin "SW2") (pinfunction "PIN-2_SW2") (pintype "bidirectional"))
    )
    (net (code "119") (name "Net-(U$73-PIN-2)") (class "Default")
      (node (ref "D73") (pin "C") (pinfunction "C_C") (pintype "passive"))
      (node (ref "U$73") (pin "SW2") (pinfunction "PIN-2_SW2") (pintype "bidirectional"))
    )
    (net (code "120") (name "Net-(U$74-PIN-2)") (class "Default")
      (node (ref "D74") (pin "C") (pinfunction "C_C") (pintype "passive"))
      (node (ref "U$74") (pin "SW2") (pinfunction "PIN-2_SW2") (pintype "bidirectional"))
    )
    (net (code "121") (name "Net-(U$75-PIN-2)") (class "Default")
      (node (ref "D75") (pin "C") (pinfunction "C_C") (pintype "passive"))
      (node (ref "U$75") (pin "SW2") (pinfunction "PIN-2_SW2") (pintype "bidirectional"))
    )
    (net (code "122") (name "Net-(U$76-PIN-2)") (class "Default")
      (node (ref "D76") (pin "C") (pinfunction "C_C") (pintype "passive"))
      (node (ref "U$76") (pin "SW2") (pinfunction "PIN-2_SW2") (pintype "bidirectional"))
    )
    (net (code "123") (name "Net-(U$77-PIN-2)") (class "Default")
      (node (ref "D77") (pin "C") (pinfunction "C_C") (pintype "passive"))
      (node (ref "U$77") (pin "SW2") (pinfunction "PIN-2_SW2") (pintype "bidirectional"))
    )
    (net (code "124") (name "Net-(U$78-PIN-2)") (class "Default")
      (node (ref "D78") (pin "C") (pinfunction "C_C") (pintype "passive"))
      (node (ref "U$78") (pin "SW2") (pinfunction "PIN-2_SW2") (pintype "bidirectional"))
    )
    (net (code "125") (name "Net-(U$79-PIN-2)") (class "Default")
      (node (ref "D79") (pin "C") (pinfunction "C_C") (pintype "passive"))
      (node (ref "U$79") (pin "SW2") (pinfunction "PIN-2_SW2") (pintype "bidirectional"))
    )
    (net (code "126") (name "Net-(U$80-PIN-2)") (class "Default")
      (node (ref "D80") (pin "C") (pinfunction "C_C") (pintype "passive"))
      (node (ref "U$80") (pin "SW2") (pinfunction "PIN-2_SW2") (pintype "bidirectional"))
    )
    (net (code "127") (name "Net-(U$81-PIN-2)") (class "Default")
      (node (ref "D81") (pin "C") (pinfunction "C_C") (pintype "passive"))
      (node (ref "U$81") (pin "SW2") (pinfunction "PIN-2_SW2") (pintype "bidirectional"))
    )
    (net (code "128") (name "Net-(U$83-PIN-2)") (class "Default")
      (node (ref "D83") (pin "C") (pinfunction "C_C") (pintype "passive"))
      (node (ref "U$83") (pin "SW2") (pinfunction "PIN-2_SW2") (pintype "bidirectional"))
    )
    (net (code "129") (name "Net-(U$84-PIN-2)") (class "Default")
      (node (ref "D84") (pin "C") (pinfunction "C_C") (pintype "passive"))
      (node (ref "U$84") (pin "SW2") (pinfunction "PIN-2_SW2") (pintype "bidirectional"))
    )
    (net (code "130") (name "Net-(U$85-PIN-2)") (class "Default")
      (node (ref "D85") (pin "C") (pinfunction "C_C") (pintype "passive"))
      (node (ref "U$85") (pin "SW2") (pinfunction "PIN-2_SW2") (pintype "bidirectional"))
    )
    (net (code "131") (name "Net-(U$86-PIN-2)") (class "Default")
      (node (ref "D86") (pin "C") (pinfunction "C_C") (pintype "passive"))
      (node (ref "U$86") (pin "SW2") (pinfunction "PIN-2_SW2") (pintype "bidirectional"))
    )
    (net (code "132") (name "Net-(U$87-PIN-2)") (class "Default")
      (node (ref "D87") (pin "C") (pinfunction "C_C") (pintype "passive"))
      (node (ref "U$87") (pin "SW2") (pinfunction "PIN-2_SW2") (pintype "bidirectional"))
    )
    (net (code "133") (name "Net-(U$88-PIN-2)") (class "Default")
      (node (ref "D88") (pin "C") (pinfunction "C_C") (pintype "passive"))
      (node (ref "U$88") (pin "SW2") (pinfunction "PIN-2_SW2") (pintype "bidirectional"))
    )
    (net (code "134") (name "Net-(U$89-PIN-2)") (class "Default")
      (node (ref "D89") (pin "C") (pinfunction "C_C") (pintype "passive"))
      (node (ref "U$89") (pin "SW2") (pinfunction "PIN-2_SW2") (pintype "bidirectional"))
    )
    (net (code "135") (name "Net-(U$90-PIN-2)") (class "Default")
      (node (ref "D90") (pin "C") (pinfunction "C_C") (pintype "passive"))
      (node (ref "U$90") (pin "SW2") (pinfunction "PIN-2_SW2") (pintype "bidirectional"))
    )
    (net (code "136") (name "Net-(U$91-PIN-2)") (class "Default")
      (node (ref "D91") (pin "C") (pinfunction "C_C") (pintype "passive"))
      (node (ref "U$91") (pin "SW2") (pinfunction "PIN-2_SW2") (pintype "bidirectional"))
    )
    (net (code "137") (name "Net-(U$92-PIN-2)") (class "Default")
      (node (ref "D92") (pin "C") (pinfunction "C_C") (pintype "passive"))
      (node (ref "U$92") (pin "SW2") (pinfunction "PIN-2_SW2") (pintype "bidirectional"))
    )
    (net (code "138") (name "Net-(U$93-PIN-2)") (class "Default")
      (node (ref "D93") (pin "C") (pinfunction "C_C") (pintype "passive"))
      (node (ref "U$93") (pin "SW2") (pinfunction "PIN-2_SW2") (pintype "bidirectional"))
    )
    (net (code "139") (name "Net-(U1-D+)") (class "Default")
      (node (ref "R1") (pin "1") (pinfunction "1_1") (pintype "passive"))
      (node (ref "U1") (pin "4") (pinfunction "D+_4") (pintype "bidirectional"))
    )
    (net (code "140") (name "Net-(U1-D-)") (class "Default")
      (node (ref "R2") (pin "1") (pinfunction "1_1") (pintype "passive"))
      (node (ref "U1") (pin "3") (pinfunction "D-_3") (pintype "bidirectional"))
    )
    (net (code "141") (name "Net-(U1-PE2)") (class "Default")
      (node (ref "R4") (pin "2") (pinfunction "2_2") (pintype "passive"))
      (node (ref "U1") (pin "33") (pinfunction "PE2_33") (pintype "bidirectional"))
    )
    (net (code "142") (name "Net-(U1-UCAP)") (class "Default")
      (node (ref "C1-1UF2") (pin "1") (pinfunction "1_1") (pintype "passive"))
      (node (ref "U1") (pin "6") (pinfunction "UCAP_6") (pintype "passive"))
    )
    (net (code "143") (name "Net-(U1-XTAL1)") (class "Default")
      (node (ref "C1-22PF2") (pin "1") (pinfunction "1_1") (pintype "passive"))
      (node (ref "U1") (pin "17") (pinfunction "XTAL1_17") (pintype "input"))
      (node (ref "Y1") (pin "2") (pinfunction "2_2") (pintype "passive"))
    )
    (net (code "144") (name "Net-(U1-XTAL2)") (class "Default")
      (node (ref "C1-22PF1") (pin "1") (pinfunction "1_1") (pintype "passive"))
      (node (ref "U1") (pin "16") (pinfunction "XTAL2_16") (pintype "output"))
      (node (ref "Y1") (pin "1") (pinfunction "1_1") (pintype "passive"))
    )
    (net (code "145") (name "VCC") (class "Default")
      (node (ref "C1-0.1U") (pin "1") (pinfunction "1_1") (pintype "passive"))
      (node (ref "C1-1UF1") (pin "1") (pinfunction "1_1") (pintype "passive"))
      (node (ref "C2-0.1U") (pin "1") (pinfunction "1_1") (pintype "passive"))
      (node (ref "C3-0.1U") (pin "1") (pinfunction "1_1") (pintype "passive"))
      (node (ref "J3") (pin "2") (pinfunction "2_2") (pintype "passive"))
      (node (ref "MULTIPLEXOR") (pin "24") (pinfunction "+UB_24") (pintype "power_in"))
      (node (ref "ONOFF") (pin "2") (pinfunction "2_2") (pintype "passive"))
      (node (ref "R5") (pin "1") (pinfunction "1_1") (pintype "passive"))
      (node (ref "U1") (pin "14") (pinfunction "VCC_14") (pintype "power_in"))
      (node (ref "U1") (pin "2") (pinfunction "UVCC_2") (pintype "power_in"))
      (node (ref "U1") (pin "24") (pinfunction "AVCC_24") (pintype "power_in"))
      (node (ref "U1") (pin "34") (pinfunction "VCC_34") (pintype "power_in"))
      (node (ref "U1") (pin "42") (pinfunction "AREF_42") (pintype "input"))
      (node (ref "U1") (pin "44") (pinfunction "AVCC_44") (pintype "power_in"))
      (node (ref "U1") (pin "7") (pinfunction "VBUS_7") (pintype "input"))
      (node (ref "X2") (pin "VBUS") (pinfunction "VBUS_VBUS") (pintype "bidirectional"))
    )
    (net (code "146") (name "unconnected-(BUTTON-P-Pad3)") (class "Default")
      (node (ref "BUTTON") (pin "3") (pinfunction "P_3") (pintype "passive"))
    )
    (net (code "147") (name "unconnected-(BUTTON-S1-Pad2)") (class "Default")
      (node (ref "BUTTON") (pin "2") (pinfunction "S1_2") (pintype "passive"))
    )
    (net (code "148") (name "unconnected-(U1-PB0-Pad8)") (class "Default")
      (node (ref "U1") (pin "8") (pinfunction "PB0_8") (pintype "bidirectional"))
    )
    (net (code "149") (name "unconnected-(U1-PD5-Pad22)") (class "Default")
      (node (ref "U1") (pin "22") (pinfunction "PD5_22") (pintype "bidirectional"))
    )
  )
)
